# Relay-Board_Rack-PDU_2_0.net
KiCad netlist of a schematic drawn in EAGLE
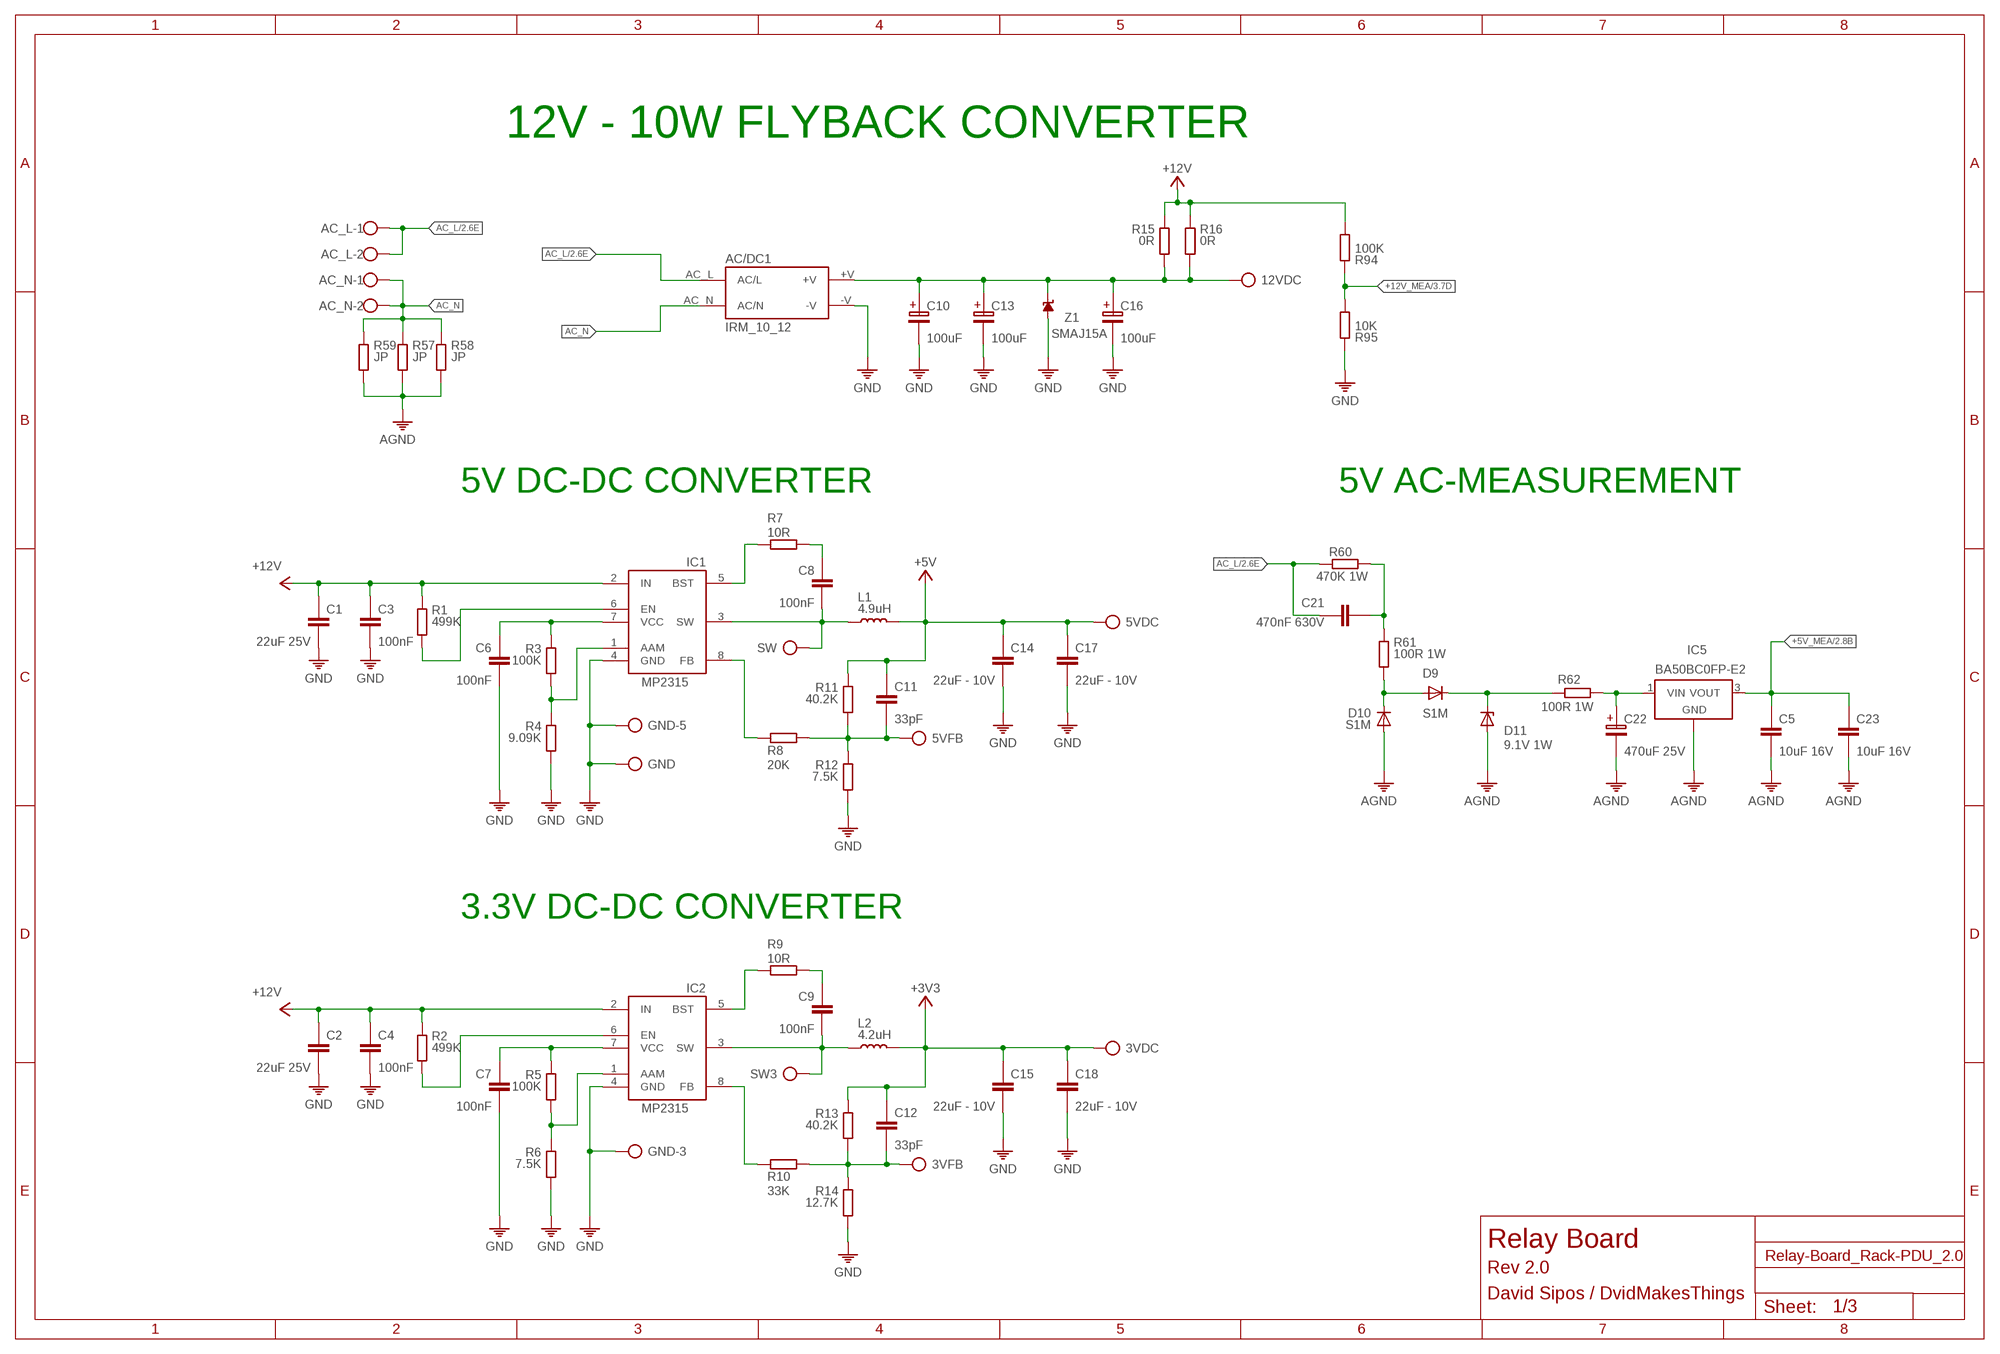
[diagram p0: schematic, sheet 1]
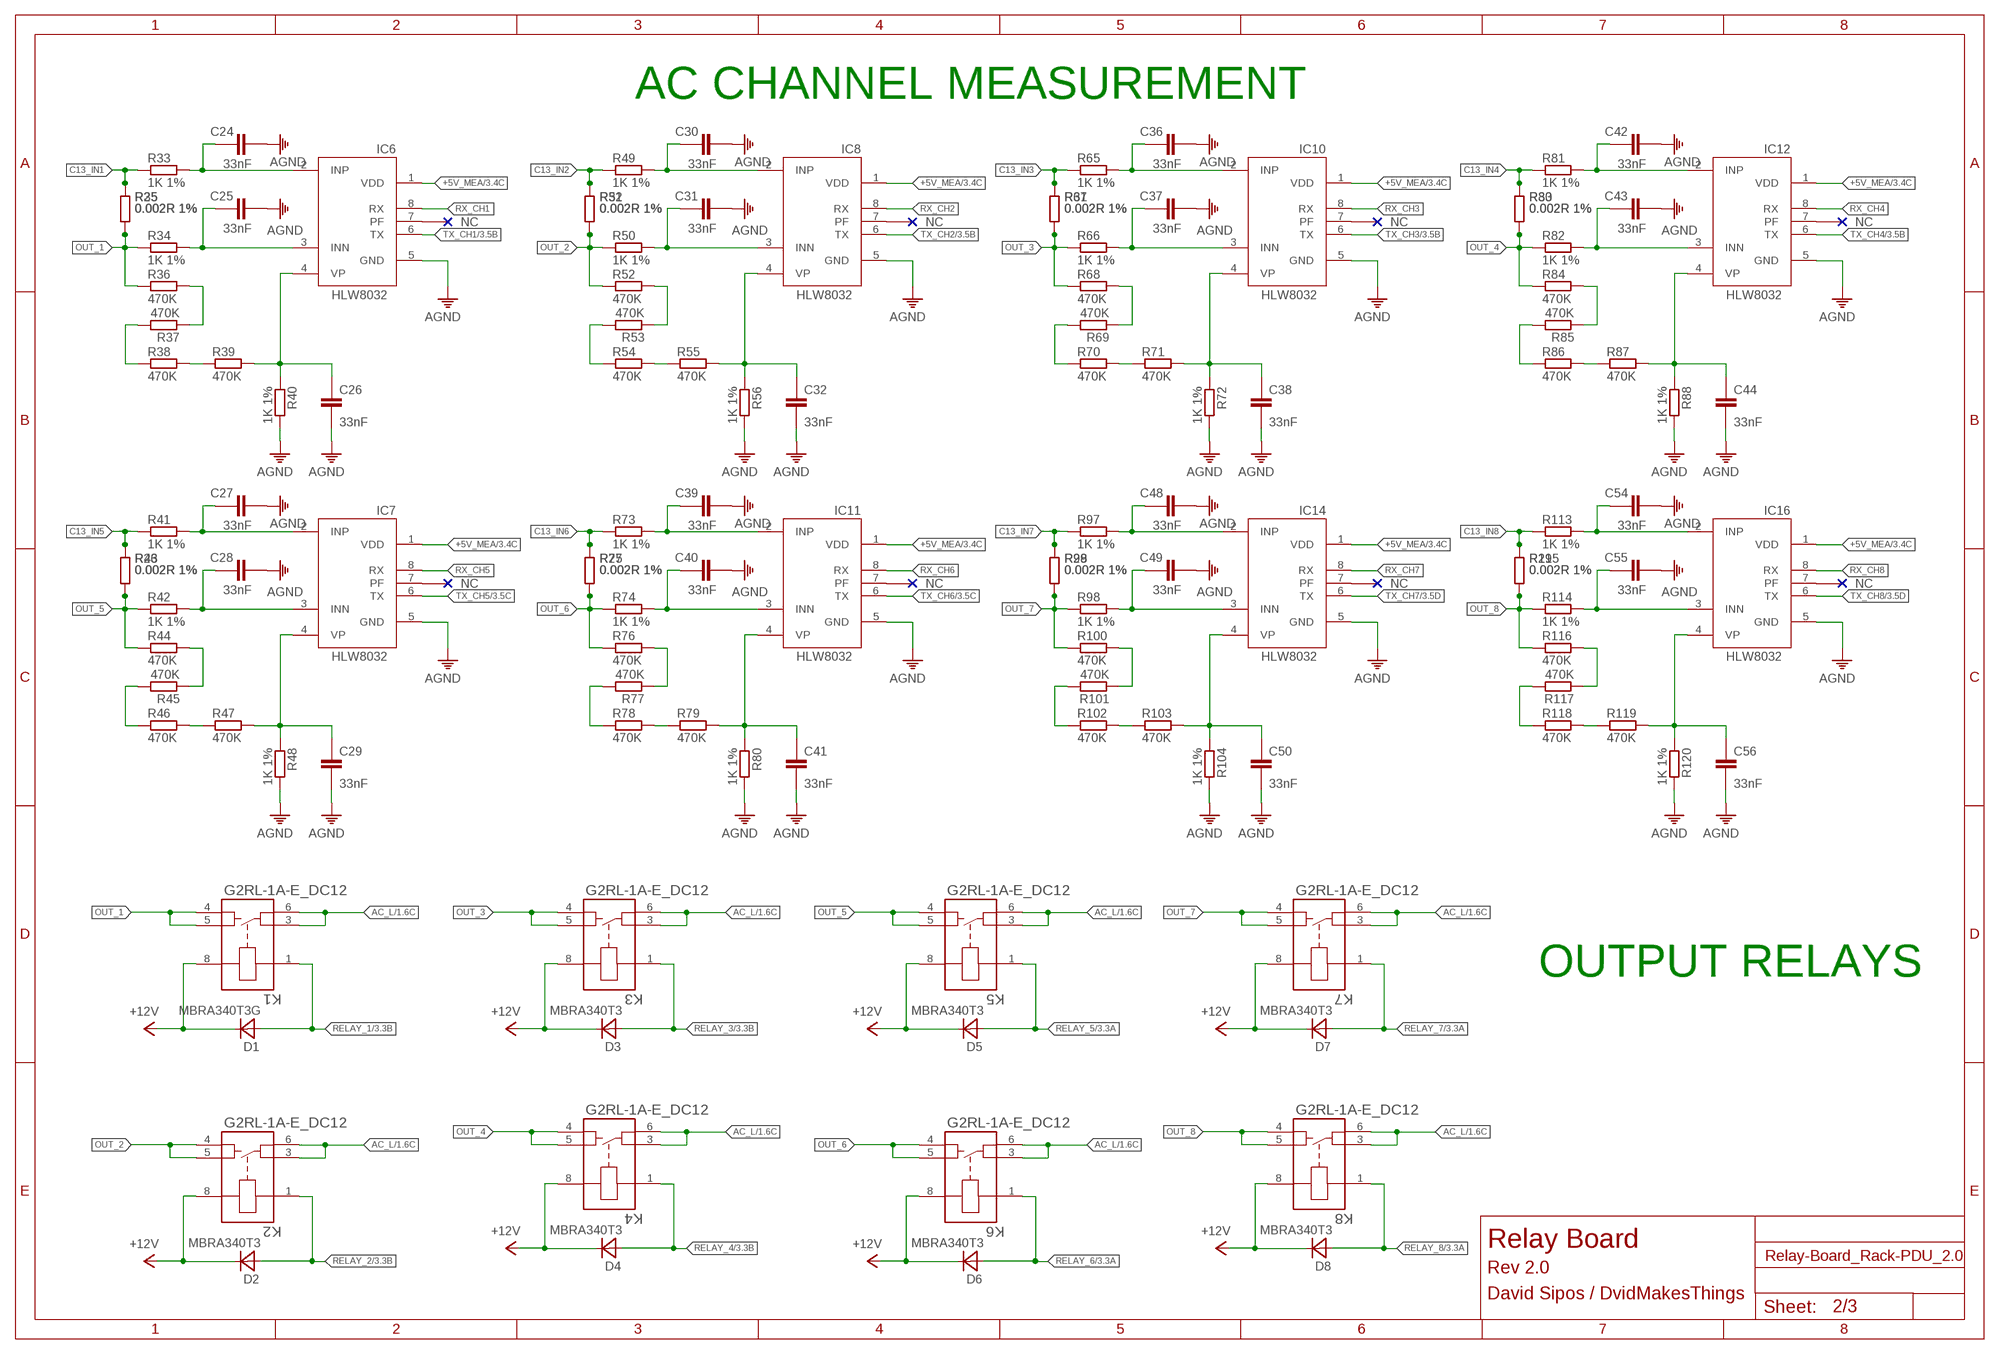
[diagram p1: schematic, sheet 2]
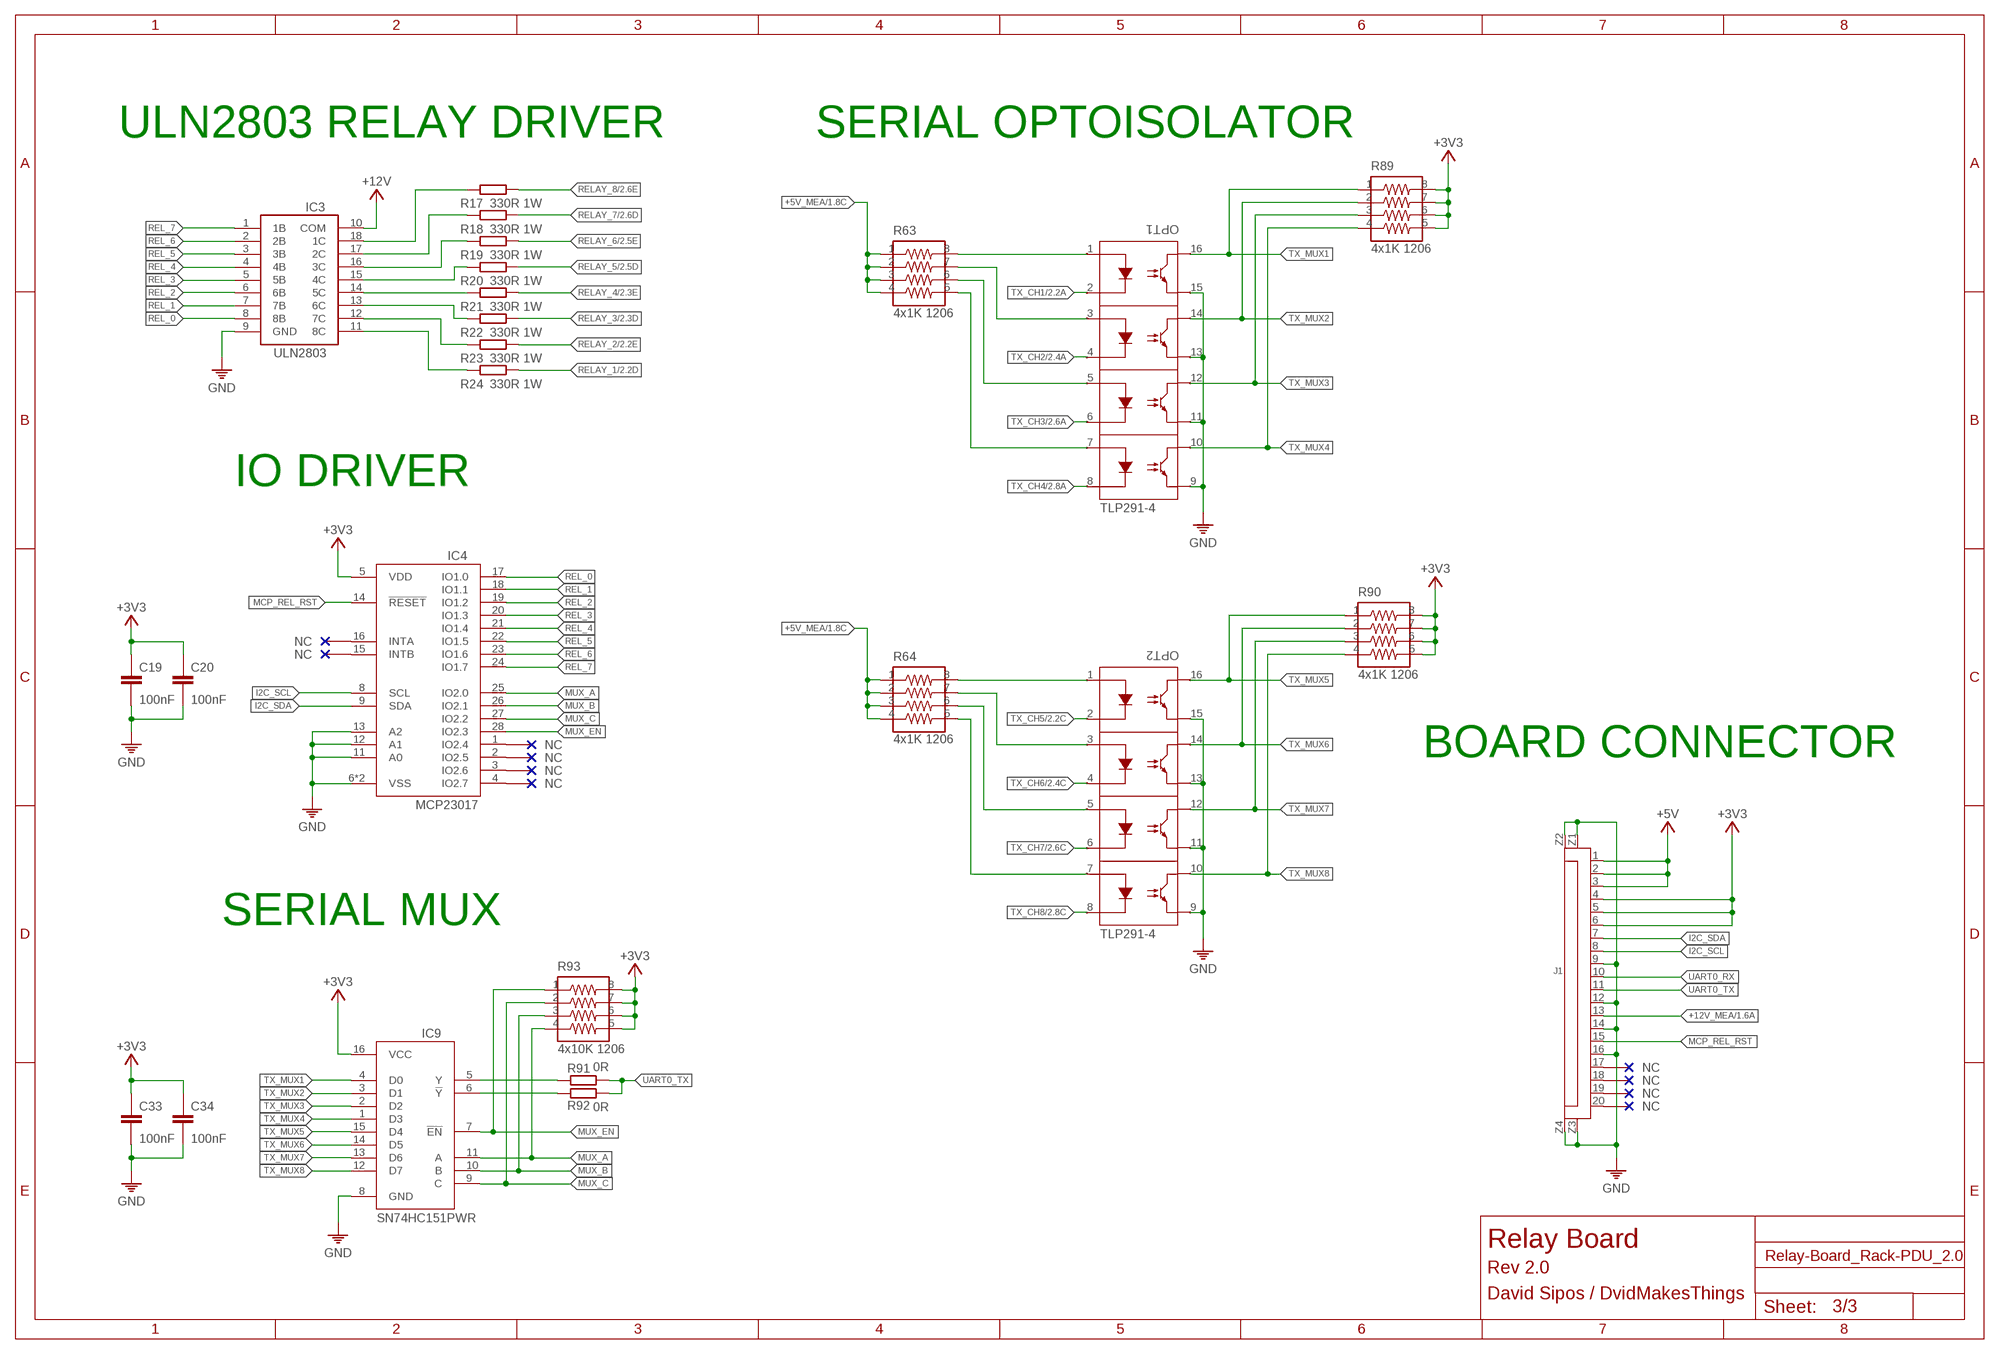
[diagram p2: schematic, sheet 3]

(export (version "E")
  (design (tool "Eeschema 10.0.6"))
  (components
    (comp (ref "C19")
      (value "100nF")
      (footprint "eagle-import:C0402")
      (libsource (lib "eagle-import") (part "C-0402"))
    )
    (comp (ref "C20")
      (value "100nF")
      (footprint "eagle-import:C0402")
      (libsource (lib "eagle-import") (part "C-0402"))
    )
    (comp (ref "C33")
      (value "100nF")
      (footprint "eagle-import:C0402")
      (libsource (lib "eagle-import") (part "C-0402"))
    )
    (comp (ref "C34")
      (value "100nF")
      (footprint "eagle-import:C0402")
      (libsource (lib "eagle-import") (part "C-0402"))
    )
    (comp (ref "IC3")
      (value "ULN2803A")
      (footprint "eagle-import:SO18")
      (libsource (lib "eagle-import") (part "ULN2803"))
    )
    (comp (ref "IC4")
      (value "MCP23017-E/ML")
      (footprint "eagle-import:QFN28[6X6]ML")
      (libsource (lib "eagle-import") (part "MCP23017-E/ML"))
    )
    (comp (ref "IC9")
      (value "SN74HC151PWR")
      (footprint "eagle-import:TSSOP16")
      (libsource (lib "eagle-import") (part "SN74HC151PWR"))
    )
    (comp (ref "J1")
      (value "FPC20-H")
      (footprint "eagle-import:FPC20")
      (libsource (lib "eagle-import") (part "FPC20-H"))
    )
    (comp (ref "OPT1")
      (value "TLP291-4")
      (footprint "eagle-import:SO16")
      (libsource (lib "eagle-import") (part "TLP291-4(GB-TP,E)1"))
    )
    (comp (ref "OPT2")
      (value "TLP291-4")
      (footprint "eagle-import:SO16")
      (libsource (lib "eagle-import") (part "TLP291-4(GB-TP,E)1"))
    )
    (comp (ref "R17")
      (value "330R 1W")
      (footprint "eagle-import:1206")
      (libsource (lib "eagle-import") (part "R1206"))
    )
    (comp (ref "R18")
      (value "330R 1W")
      (footprint "eagle-import:1206")
      (libsource (lib "eagle-import") (part "R1206"))
    )
    (comp (ref "R19")
      (value "330R 1W")
      (footprint "eagle-import:1206")
      (libsource (lib "eagle-import") (part "R1206"))
    )
    (comp (ref "R20")
      (value "330R 1W")
      (footprint "eagle-import:1206")
      (libsource (lib "eagle-import") (part "R1206"))
    )
    (comp (ref "R21")
      (value "330R 1W")
      (footprint "eagle-import:1206")
      (libsource (lib "eagle-import") (part "R1206"))
    )
    (comp (ref "R22")
      (value "330R 1W")
      (footprint "eagle-import:1206")
      (libsource (lib "eagle-import") (part "R1206"))
    )
    (comp (ref "R23")
      (value "330R 1W")
      (footprint "eagle-import:1206")
      (libsource (lib "eagle-import") (part "R1206"))
    )
    (comp (ref "R24")
      (value "330R 1W")
      (footprint "eagle-import:1206")
      (libsource (lib "eagle-import") (part "R1206"))
    )
    (comp (ref "R63")
      (value "4x1K 1206")
      (footprint "eagle-import:742C083103JP")
      (fields
        (field (name "MANUFACTURER") "CTS Resistor Products")
        (field (name "MPN") "742C083103JP")
        (field (name "CREATED_BY") "PCBLayout.com")
      )
      (libsource (lib "eagle-import") (part "742C083103JP"))
    )
    (comp (ref "R64")
      (value "4x1K 1206")
      (footprint "eagle-import:742C083103JP")
      (fields
        (field (name "MANUFACTURER") "CTS Resistor Products")
        (field (name "MPN") "742C083103JP")
        (field (name "CREATED_BY") "PCBLayout.com")
      )
      (libsource (lib "eagle-import") (part "742C083103JP"))
    )
    (comp (ref "R89")
      (value "4x1K 1206")
      (footprint "eagle-import:742C083103JP")
      (fields
        (field (name "MANUFACTURER") "CTS Resistor Products")
        (field (name "MPN") "742C083103JP")
        (field (name "CREATED_BY") "PCBLayout.com")
      )
      (libsource (lib "eagle-import") (part "742C083103JP"))
    )
    (comp (ref "R90")
      (value "4x1K 1206")
      (footprint "eagle-import:742C083103JP")
      (fields
        (field (name "MANUFACTURER") "CTS Resistor Products")
        (field (name "MPN") "742C083103JP")
        (field (name "CREATED_BY") "PCBLayout.com")
      )
      (libsource (lib "eagle-import") (part "742C083103JP"))
    )
    (comp (ref "R91")
      (value "0R")
      (footprint "eagle-import:0402")
      (libsource (lib "eagle-import") (part "R0402"))
    )
    (comp (ref "R92")
      (value "0R")
      (footprint "eagle-import:0402")
      (libsource (lib "eagle-import") (part "R0402"))
    )
    (comp (ref "R93")
      (value "4x10K 1206")
      (footprint "eagle-import:742C083103JP")
      (fields
        (field (name "MANUFACTURER") "CTS Resistor Products")
        (field (name "MPN") "742C083103JP")
        (field (name "CREATED_BY") "PCBLayout.com")
      )
      (libsource (lib "eagle-import") (part "742C083103JP"))
    )
    (comp (ref "C24")
      (value "33nF")
      (footprint "eagle-import:C1206")
      (libsource (lib "eagle-import") (part "C-1206"))
    )
    (comp (ref "C25")
      (value "33nF")
      (footprint "eagle-import:C1206")
      (libsource (lib "eagle-import") (part "C-1206"))
    )
    (comp (ref "C26")
      (value "33nF")
      (footprint "eagle-import:C1206")
      (libsource (lib "eagle-import") (part "C-1206"))
    )
    (comp (ref "C27")
      (value "33nF")
      (footprint "eagle-import:C1206")
      (libsource (lib "eagle-import") (part "C-1206"))
    )
    (comp (ref "C28")
      (value "33nF")
      (footprint "eagle-import:C1206")
      (libsource (lib "eagle-import") (part "C-1206"))
    )
    (comp (ref "C29")
      (value "33nF")
      (footprint "eagle-import:C1206")
      (libsource (lib "eagle-import") (part "C-1206"))
    )
    (comp (ref "C30")
      (value "33nF")
      (footprint "eagle-import:C1206")
      (libsource (lib "eagle-import") (part "C-1206"))
    )
    (comp (ref "C31")
      (value "33nF")
      (footprint "eagle-import:C1206")
      (libsource (lib "eagle-import") (part "C-1206"))
    )
    (comp (ref "C32")
      (value "33nF")
      (footprint "eagle-import:C1206")
      (libsource (lib "eagle-import") (part "C-1206"))
    )
    (comp (ref "C36")
      (value "33nF")
      (footprint "eagle-import:C1206")
      (libsource (lib "eagle-import") (part "C-1206"))
    )
    (comp (ref "C37")
      (value "33nF")
      (footprint "eagle-import:C1206")
      (libsource (lib "eagle-import") (part "C-1206"))
    )
    (comp (ref "C38")
      (value "33nF")
      (footprint "eagle-import:C1206")
      (libsource (lib "eagle-import") (part "C-1206"))
    )
    (comp (ref "C39")
      (value "33nF")
      (footprint "eagle-import:C1206")
      (libsource (lib "eagle-import") (part "C-1206"))
    )
    (comp (ref "C40")
      (value "33nF")
      (footprint "eagle-import:C1206")
      (libsource (lib "eagle-import") (part "C-1206"))
    )
    (comp (ref "C41")
      (value "33nF")
      (footprint "eagle-import:C1206")
      (libsource (lib "eagle-import") (part "C-1206"))
    )
    (comp (ref "C42")
      (value "33nF")
      (footprint "eagle-import:C1206")
      (libsource (lib "eagle-import") (part "C-1206"))
    )
    (comp (ref "C43")
      (value "33nF")
      (footprint "eagle-import:C1206")
      (libsource (lib "eagle-import") (part "C-1206"))
    )
    (comp (ref "C44")
      (value "33nF")
      (footprint "eagle-import:C1206")
      (libsource (lib "eagle-import") (part "C-1206"))
    )
    (comp (ref "C48")
      (value "33nF")
      (footprint "eagle-import:C1206")
      (libsource (lib "eagle-import") (part "C-1206"))
    )
    (comp (ref "C49")
      (value "33nF")
      (footprint "eagle-import:C1206")
      (libsource (lib "eagle-import") (part "C-1206"))
    )
    (comp (ref "C50")
      (value "33nF")
      (footprint "eagle-import:C1206")
      (libsource (lib "eagle-import") (part "C-1206"))
    )
    (comp (ref "C54")
      (value "33nF")
      (footprint "eagle-import:C1206")
      (libsource (lib "eagle-import") (part "C-1206"))
    )
    (comp (ref "C55")
      (value "33nF")
      (footprint "eagle-import:C1206")
      (libsource (lib "eagle-import") (part "C-1206"))
    )
    (comp (ref "C56")
      (value "33nF")
      (footprint "eagle-import:C1206")
      (libsource (lib "eagle-import") (part "C-1206"))
    )
    (comp (ref "D1")
      (value "MBRA340T3G")
      (footprint "eagle-import:SMA")
      (libsource (lib "eagle-import") (part "MBRA340T3"))
    )
    (comp (ref "D2")
      (value "MBRA340T3")
      (footprint "eagle-import:SMA")
      (libsource (lib "eagle-import") (part "MBRA340T3"))
    )
    (comp (ref "D3")
      (value "MBRA340T3")
      (footprint "eagle-import:SMA")
      (libsource (lib "eagle-import") (part "MBRA340T3"))
    )
    (comp (ref "D4")
      (value "MBRA340T3")
      (footprint "eagle-import:SMA")
      (libsource (lib "eagle-import") (part "MBRA340T3"))
    )
    (comp (ref "D5")
      (value "MBRA340T3")
      (footprint "eagle-import:SMA")
      (libsource (lib "eagle-import") (part "MBRA340T3"))
    )
    (comp (ref "D6")
      (value "MBRA340T3")
      (footprint "eagle-import:SMA")
      (libsource (lib "eagle-import") (part "MBRA340T3"))
    )
    (comp (ref "D7")
      (value "MBRA340T3")
      (footprint "eagle-import:SMA")
      (libsource (lib "eagle-import") (part "MBRA340T3"))
    )
    (comp (ref "D8")
      (value "MBRA340T3")
      (footprint "eagle-import:SMA")
      (libsource (lib "eagle-import") (part "MBRA340T3"))
    )
    (comp (ref "IC6")
      (value "HLW8032")
      (footprint "eagle-import:SO8")
      (libsource (lib "eagle-import") (part "HLW8032"))
    )
    (comp (ref "IC7")
      (value "HLW8032")
      (footprint "eagle-import:SO8")
      (libsource (lib "eagle-import") (part "HLW8032"))
    )
    (comp (ref "IC8")
      (value "HLW8032")
      (footprint "eagle-import:SO8")
      (libsource (lib "eagle-import") (part "HLW8032"))
    )
    (comp (ref "IC10")
      (value "HLW8032")
      (footprint "eagle-import:SO8")
      (libsource (lib "eagle-import") (part "HLW8032"))
    )
    (comp (ref "IC11")
      (value "HLW8032")
      (footprint "eagle-import:SO8")
      (libsource (lib "eagle-import") (part "HLW8032"))
    )
    (comp (ref "IC12")
      (value "HLW8032")
      (footprint "eagle-import:SO8")
      (libsource (lib "eagle-import") (part "HLW8032"))
    )
    (comp (ref "IC14")
      (value "HLW8032")
      (footprint "eagle-import:SO8")
      (libsource (lib "eagle-import") (part "HLW8032"))
    )
    (comp (ref "IC16")
      (value "HLW8032")
      (footprint "eagle-import:SO8")
      (libsource (lib "eagle-import") (part "HLW8032"))
    )
    (comp (ref "K1")
      (value "G2RL-1A-E_DC12")
      (footprint "eagle-import:RELAY_G2RL-1A-E_DC5_OMR")
      (fields
        (field (name "MANUFACTURER_PART_NUMBER") "G2RL-1A-E DC12")
        (field (name "COPYRIGHT") "Copyright (C) 2025 Ultra Librarian. All rights reserved.")
      )
      (libsource (lib "eagle-import") (part "G2RL-1A-E_DC12"))
    )
    (comp (ref "K2")
      (value "G2RL-1A-E_DC12")
      (footprint "eagle-import:RELAY_G2RL-1A-E_DC5_OMR")
      (fields
        (field (name "MANUFACTURER_PART_NUMBER") "G2RL-1A-E DC12")
        (field (name "COPYRIGHT") "Copyright (C) 2025 Ultra Librarian. All rights reserved.")
      )
      (libsource (lib "eagle-import") (part "G2RL-1A-E_DC12"))
    )
    (comp (ref "K3")
      (value "G2RL-1A-E_DC12")
      (footprint "eagle-import:RELAY_G2RL-1A-E_DC5_OMR")
      (fields
        (field (name "MANUFACTURER_PART_NUMBER") "G2RL-1A-E DC12")
        (field (name "COPYRIGHT") "Copyright (C) 2025 Ultra Librarian. All rights reserved.")
      )
      (libsource (lib "eagle-import") (part "G2RL-1A-E_DC12"))
    )
    (comp (ref "K4")
      (value "G2RL-1A-E_DC12")
      (footprint "eagle-import:RELAY_G2RL-1A-E_DC5_OMR")
      (fields
        (field (name "MANUFACTURER_PART_NUMBER") "G2RL-1A-E DC12")
        (field (name "COPYRIGHT") "Copyright (C) 2025 Ultra Librarian. All rights reserved.")
      )
      (libsource (lib "eagle-import") (part "G2RL-1A-E_DC12"))
    )
    (comp (ref "K5")
      (value "G2RL-1A-E_DC12")
      (footprint "eagle-import:RELAY_G2RL-1A-E_DC5_OMR")
      (fields
        (field (name "MANUFACTURER_PART_NUMBER") "G2RL-1A-E DC12")
        (field (name "COPYRIGHT") "Copyright (C) 2025 Ultra Librarian. All rights reserved.")
      )
      (libsource (lib "eagle-import") (part "G2RL-1A-E_DC12"))
    )
    (comp (ref "K6")
      (value "G2RL-1A-E_DC12")
      (footprint "eagle-import:RELAY_G2RL-1A-E_DC5_OMR")
      (fields
        (field (name "MANUFACTURER_PART_NUMBER") "G2RL-1A-E DC12")
        (field (name "COPYRIGHT") "Copyright (C) 2025 Ultra Librarian. All rights reserved.")
      )
      (libsource (lib "eagle-import") (part "G2RL-1A-E_DC12"))
    )
    (comp (ref "K7")
      (value "G2RL-1A-E_DC12")
      (footprint "eagle-import:RELAY_G2RL-1A-E_DC5_OMR")
      (fields
        (field (name "MANUFACTURER_PART_NUMBER") "G2RL-1A-E DC12")
        (field (name "COPYRIGHT") "Copyright (C) 2025 Ultra Librarian. All rights reserved.")
      )
      (libsource (lib "eagle-import") (part "G2RL-1A-E_DC12"))
    )
    (comp (ref "K8")
      (value "G2RL-1A-E_DC12")
      (footprint "eagle-import:RELAY_G2RL-1A-E_DC5_OMR")
      (fields
        (field (name "MANUFACTURER_PART_NUMBER") "G2RL-1A-E DC12")
        (field (name "COPYRIGHT") "Copyright (C) 2025 Ultra Librarian. All rights reserved.")
      )
      (libsource (lib "eagle-import") (part "G2RL-1A-E_DC12"))
    )
    (comp (ref "R25")
      (value "0.002R 1%")
      (footprint "eagle-import:2512")
      (libsource (lib "eagle-import") (part "R2512"))
    )
    (comp (ref "R26")
      (value "0.002R 1%")
      (footprint "eagle-import:2512")
      (libsource (lib "eagle-import") (part "R2512"))
    )
    (comp (ref "R27")
      (value "0.002R 1%")
      (footprint "eagle-import:2512")
      (libsource (lib "eagle-import") (part "R2512"))
    )
    (comp (ref "R28")
      (value "0.002R 1%")
      (footprint "eagle-import:2512")
      (libsource (lib "eagle-import") (part "R2512"))
    )
    (comp (ref "R29")
      (value "0.002R 1%")
      (footprint "eagle-import:2512")
      (libsource (lib "eagle-import") (part "R2512"))
    )
    (comp (ref "R30")
      (value "0.002R 1%")
      (footprint "eagle-import:2512")
      (libsource (lib "eagle-import") (part "R2512"))
    )
    (comp (ref "R31")
      (value "0.002R 1%")
      (footprint "eagle-import:2512")
      (libsource (lib "eagle-import") (part "R2512"))
    )
    (comp (ref "R32")
      (value "0.002R 1%")
      (footprint "eagle-import:2512")
      (libsource (lib "eagle-import") (part "R2512"))
    )
    (comp (ref "R33")
      (value "1K 1%")
      (footprint "eagle-import:1206")
      (libsource (lib "eagle-import") (part "R1206"))
    )
    (comp (ref "R34")
      (value "1K 1%")
      (footprint "eagle-import:1206")
      (libsource (lib "eagle-import") (part "R1206"))
    )
    (comp (ref "R35")
      (value "0.002R 1%")
      (footprint "eagle-import:2512")
      (libsource (lib "eagle-import") (part "R2512"))
    )
    (comp (ref "R36")
      (value "470K")
      (footprint "eagle-import:1206")
      (libsource (lib "eagle-import") (part "R1206"))
    )
    (comp (ref "R37")
      (value "470K")
      (footprint "eagle-import:1206")
      (libsource (lib "eagle-import") (part "R1206"))
    )
    (comp (ref "R38")
      (value "470K")
      (footprint "eagle-import:1206")
      (libsource (lib "eagle-import") (part "R1206"))
    )
    (comp (ref "R39")
      (value "470K")
      (footprint "eagle-import:1206")
      (libsource (lib "eagle-import") (part "R1206"))
    )
    (comp (ref "R40")
      (value "1K 1%")
      (footprint "eagle-import:1206")
      (libsource (lib "eagle-import") (part "R1206"))
    )
    (comp (ref "R41")
      (value "1K 1%")
      (footprint "eagle-import:1206")
      (libsource (lib "eagle-import") (part "R1206"))
    )
    (comp (ref "R42")
      (value "1K 1%")
      (footprint "eagle-import:1206")
      (libsource (lib "eagle-import") (part "R1206"))
    )
    (comp (ref "R43")
      (value "0.002R 1%")
      (footprint "eagle-import:2512")
      (libsource (lib "eagle-import") (part "R2512"))
    )
    (comp (ref "R44")
      (value "470K")
      (footprint "eagle-import:1206")
      (libsource (lib "eagle-import") (part "R1206"))
    )
    (comp (ref "R45")
      (value "470K")
      (footprint "eagle-import:1206")
      (libsource (lib "eagle-import") (part "R1206"))
    )
    (comp (ref "R46")
      (value "470K")
      (footprint "eagle-import:1206")
      (libsource (lib "eagle-import") (part "R1206"))
    )
    (comp (ref "R47")
      (value "470K")
      (footprint "eagle-import:1206")
      (libsource (lib "eagle-import") (part "R1206"))
    )
    (comp (ref "R48")
      (value "1K 1%")
      (footprint "eagle-import:1206")
      (libsource (lib "eagle-import") (part "R1206"))
    )
    (comp (ref "R49")
      (value "1K 1%")
      (footprint "eagle-import:1206")
      (libsource (lib "eagle-import") (part "R1206"))
    )
    (comp (ref "R50")
      (value "1K 1%")
      (footprint "eagle-import:1206")
      (libsource (lib "eagle-import") (part "R1206"))
    )
    (comp (ref "R51")
      (value "0.002R 1%")
      (footprint "eagle-import:2512")
      (libsource (lib "eagle-import") (part "R2512"))
    )
    (comp (ref "R52")
      (value "470K")
      (footprint "eagle-import:1206")
      (libsource (lib "eagle-import") (part "R1206"))
    )
    (comp (ref "R53")
      (value "470K")
      (footprint "eagle-import:1206")
      (libsource (lib "eagle-import") (part "R1206"))
    )
    (comp (ref "R54")
      (value "470K")
      (footprint "eagle-import:1206")
      (libsource (lib "eagle-import") (part "R1206"))
    )
    (comp (ref "R55")
      (value "470K")
      (footprint "eagle-import:1206")
      (libsource (lib "eagle-import") (part "R1206"))
    )
    (comp (ref "R56")
      (value "1K 1%")
      (footprint "eagle-import:1206")
      (libsource (lib "eagle-import") (part "R1206"))
    )
    (comp (ref "R65")
      (value "1K 1%")
      (footprint "eagle-import:1206")
      (libsource (lib "eagle-import") (part "R1206"))
    )
    (comp (ref "R66")
      (value "1K 1%")
      (footprint "eagle-import:1206")
      (libsource (lib "eagle-import") (part "R1206"))
    )
    (comp (ref "R67")
      (value "0.002R 1%")
      (footprint "eagle-import:2512")
      (libsource (lib "eagle-import") (part "R2512"))
    )
    (comp (ref "R68")
      (value "470K")
      (footprint "eagle-import:1206")
      (libsource (lib "eagle-import") (part "R1206"))
    )
    (comp (ref "R69")
      (value "470K")
      (footprint "eagle-import:1206")
      (libsource (lib "eagle-import") (part "R1206"))
    )
    (comp (ref "R70")
      (value "470K")
      (footprint "eagle-import:1206")
      (libsource (lib "eagle-import") (part "R1206"))
    )
    (comp (ref "R71")
      (value "470K")
      (footprint "eagle-import:1206")
      (libsource (lib "eagle-import") (part "R1206"))
    )
    (comp (ref "R72")
      (value "1K 1%")
      (footprint "eagle-import:1206")
      (libsource (lib "eagle-import") (part "R1206"))
    )
    (comp (ref "R73")
      (value "1K 1%")
      (footprint "eagle-import:1206")
      (libsource (lib "eagle-import") (part "R1206"))
    )
    (comp (ref "R74")
      (value "1K 1%")
      (footprint "eagle-import:1206")
      (libsource (lib "eagle-import") (part "R1206"))
    )
    (comp (ref "R75")
      (value "0.002R 1%")
      (footprint "eagle-import:2512")
      (libsource (lib "eagle-import") (part "R2512"))
    )
    (comp (ref "R76")
      (value "470K")
      (footprint "eagle-import:1206")
      (libsource (lib "eagle-import") (part "R1206"))
    )
    (comp (ref "R77")
      (value "470K")
      (footprint "eagle-import:1206")
      (libsource (lib "eagle-import") (part "R1206"))
    )
    (comp (ref "R78")
      (value "470K")
      (footprint "eagle-import:1206")
      (libsource (lib "eagle-import") (part "R1206"))
    )
    (comp (ref "R79")
      (value "470K")
      (footprint "eagle-import:1206")
      (libsource (lib "eagle-import") (part "R1206"))
    )
    (comp (ref "R80")
      (value "1K 1%")
      (footprint "eagle-import:1206")
      (libsource (lib "eagle-import") (part "R1206"))
    )
    (comp (ref "R81")
      (value "1K 1%")
      (footprint "eagle-import:1206")
      (libsource (lib "eagle-import") (part "R1206"))
    )
    (comp (ref "R82")
      (value "1K 1%")
      (footprint "eagle-import:1206")
      (libsource (lib "eagle-import") (part "R1206"))
    )
    (comp (ref "R83")
      (value "0.002R 1%")
      (footprint "eagle-import:2512")
      (libsource (lib "eagle-import") (part "R2512"))
    )
    (comp (ref "R84")
      (value "470K")
      (footprint "eagle-import:1206")
      (libsource (lib "eagle-import") (part "R1206"))
    )
    (comp (ref "R85")
      (value "470K")
      (footprint "eagle-import:1206")
      (libsource (lib "eagle-import") (part "R1206"))
    )
    (comp (ref "R86")
      (value "470K")
      (footprint "eagle-import:1206")
      (libsource (lib "eagle-import") (part "R1206"))
    )
    (comp (ref "R87")
      (value "470K")
      (footprint "eagle-import:1206")
      (libsource (lib "eagle-import") (part "R1206"))
    )
    (comp (ref "R88")
      (value "1K 1%")
      (footprint "eagle-import:1206")
      (libsource (lib "eagle-import") (part "R1206"))
    )
    (comp (ref "R97")
      (value "1K 1%")
      (footprint "eagle-import:1206")
      (libsource (lib "eagle-import") (part "R1206"))
    )
    (comp (ref "R98")
      (value "1K 1%")
      (footprint "eagle-import:1206")
      (libsource (lib "eagle-import") (part "R1206"))
    )
    (comp (ref "R99")
      (value "0.002R 1%")
      (footprint "eagle-import:2512")
      (libsource (lib "eagle-import") (part "R2512"))
    )
    (comp (ref "R100")
      (value "470K")
      (footprint "eagle-import:1206")
      (libsource (lib "eagle-import") (part "R1206"))
    )
    (comp (ref "R101")
      (value "470K")
      (footprint "eagle-import:1206")
      (libsource (lib "eagle-import") (part "R1206"))
    )
    (comp (ref "R102")
      (value "470K")
      (footprint "eagle-import:1206")
      (libsource (lib "eagle-import") (part "R1206"))
    )
    (comp (ref "R103")
      (value "470K")
      (footprint "eagle-import:1206")
      (libsource (lib "eagle-import") (part "R1206"))
    )
    (comp (ref "R104")
      (value "1K 1%")
      (footprint "eagle-import:1206")
      (libsource (lib "eagle-import") (part "R1206"))
    )
    (comp (ref "R113")
      (value "1K 1%")
      (footprint "eagle-import:1206")
      (libsource (lib "eagle-import") (part "R1206"))
    )
    (comp (ref "R114")
      (value "1K 1%")
      (footprint "eagle-import:1206")
      (libsource (lib "eagle-import") (part "R1206"))
    )
    (comp (ref "R115")
      (value "0.002R 1%")
      (footprint "eagle-import:2512")
      (libsource (lib "eagle-import") (part "R2512"))
    )
    (comp (ref "R116")
      (value "470K")
      (footprint "eagle-import:1206")
      (libsource (lib "eagle-import") (part "R1206"))
    )
    (comp (ref "R117")
      (value "470K")
      (footprint "eagle-import:1206")
      (libsource (lib "eagle-import") (part "R1206"))
    )
    (comp (ref "R118")
      (value "470K")
      (footprint "eagle-import:1206")
      (libsource (lib "eagle-import") (part "R1206"))
    )
    (comp (ref "R119")
      (value "470K")
      (footprint "eagle-import:1206")
      (libsource (lib "eagle-import") (part "R1206"))
    )
    (comp (ref "R120")
      (value "1K 1%")
      (footprint "eagle-import:1206")
      (libsource (lib "eagle-import") (part "R1206"))
    )
    (comp (ref "3VDC")
      (value "TP")
      (footprint "eagle-import:TP")
      (libsource (lib "eagle-import") (part "TP"))
    )
    (comp (ref "3VFB")
      (value "TP")
      (footprint "eagle-import:TP")
      (libsource (lib "eagle-import") (part "TP"))
    )
    (comp (ref "5VDC")
      (value "TP")
      (footprint "eagle-import:TP")
      (libsource (lib "eagle-import") (part "TP"))
    )
    (comp (ref "5VFB")
      (value "TP")
      (footprint "eagle-import:TP")
      (libsource (lib "eagle-import") (part "TP"))
    )
    (comp (ref "12VDC")
      (value "TP")
      (footprint "eagle-import:TP")
      (libsource (lib "eagle-import") (part "TP"))
    )
    (comp (ref "AC/DC1")
      (value "IRM_10_12")
      (footprint "eagle-import:IRM_10_12")
      (libsource (lib "eagle-import") (part "IRM_10_12"))
    )
    (comp (ref "AC_L")
      (value "W237-102")
      (footprint "eagle-import:W237-102")
      (fields (field (name "MPN") "237-102"))
      (libsource (lib "eagle-import") (part "W237-102"))
    )
    (comp (ref "AC_N")
      (value "W237-102")
      (footprint "eagle-import:W237-102")
      (fields (field (name "MPN") "237-102"))
      (libsource (lib "eagle-import") (part "W237-102"))
    )
    (comp (ref "C1")
      (value "22uF 25V")
      (footprint "eagle-import:C1206")
      (libsource (lib "eagle-import") (part "C-1206"))
    )
    (comp (ref "C2")
      (value "22uF 25V")
      (footprint "eagle-import:C1206")
      (libsource (lib "eagle-import") (part "C-1206"))
    )
    (comp (ref "C3")
      (value "100nF")
      (footprint "eagle-import:0402")
      (libsource (lib "eagle-import") (part "C0402"))
    )
    (comp (ref "C4")
      (value "100nF")
      (footprint "eagle-import:0402")
      (libsource (lib "eagle-import") (part "C0402"))
    )
    (comp (ref "C5")
      (value "10uF 16V")
      (footprint "eagle-import:C1206")
      (libsource (lib "eagle-import") (part "C-1206"))
    )
    (comp (ref "C6")
      (value "100nF")
      (footprint "eagle-import:0402")
      (libsource (lib "eagle-import") (part "C0402"))
    )
    (comp (ref "C7")
      (value "100nF")
      (footprint "eagle-import:0402")
      (libsource (lib "eagle-import") (part "C0402"))
    )
    (comp (ref "C8")
      (value "100nF")
      (footprint "eagle-import:0402")
      (libsource (lib "eagle-import") (part "C0402"))
    )
    (comp (ref "C9")
      (value "100nF")
      (footprint "eagle-import:0402")
      (libsource (lib "eagle-import") (part "C0402"))
    )
    (comp (ref "C10")
      (value "100uF")
      (footprint "eagle-import:100UF-16V")
      (libsource (lib "eagle-import") (part "CPOL"))
    )
    (comp (ref "C11")
      (value "33pF")
      (footprint "eagle-import:0402")
      (libsource (lib "eagle-import") (part "C0402"))
    )
    (comp (ref "C12")
      (value "33pF")
      (footprint "eagle-import:0402")
      (libsource (lib "eagle-import") (part "C0402"))
    )
    (comp (ref "C13")
      (value "100uF")
      (footprint "eagle-import:100UF-16V")
      (libsource (lib "eagle-import") (part "CPOL"))
    )
    (comp (ref "C14")
      (value "22uF - 10V")
      (footprint "eagle-import:C1206")
      (libsource (lib "eagle-import") (part "C-1206"))
    )
    (comp (ref "C15")
      (value "22uF - 10V")
      (footprint "eagle-import:C1206")
      (libsource (lib "eagle-import") (part "C-1206"))
    )
    (comp (ref "C16")
      (value "100uF")
      (footprint "eagle-import:100UF-16V")
      (libsource (lib "eagle-import") (part "CPOL"))
    )
    (comp (ref "C17")
      (value "22uF - 10V")
      (footprint "eagle-import:C1206")
      (libsource (lib "eagle-import") (part "C-1206"))
    )
    (comp (ref "C18")
      (value "22uF - 10V")
      (footprint "eagle-import:C1206")
      (libsource (lib "eagle-import") (part "C-1206"))
    )
    (comp (ref "C21")
      (value "470nF 630V")
      (footprint "eagle-import:2225")
      (libsource (lib "eagle-import") (part "C-2225"))
    )
    (comp (ref "C22")
      (value "470uF 25V")
      (footprint "eagle-import:100UF-16V")
      (libsource (lib "eagle-import") (part "CPOL"))
    )
    (comp (ref "C23")
      (value "10uF 16V")
      (footprint "eagle-import:C1206")
      (libsource (lib "eagle-import") (part "C-1206"))
    )
    (comp (ref "D9")
      (value "S1M")
      (footprint "eagle-import:SMA")
      (libsource (lib "eagle-import") (part "S1M"))
    )
    (comp (ref "D10")
      (value "S1M")
      (footprint "eagle-import:SMA")
      (libsource (lib "eagle-import") (part "S1M"))
    )
    (comp (ref "D11")
      (value "9.1V 1W")
      (footprint "eagle-import:SMB")
      (libsource (lib "eagle-import") (part "ZENER-DIODESMB"))
    )
    (comp (ref "GND") (value "TP") (footprint "eagle-import:TP") (libsource (lib "eagle-import") (part "TP")))
    (comp (ref "GND-3")
      (value "TP")
      (footprint "eagle-import:TP")
      (libsource (lib "eagle-import") (part "TP"))
    )
    (comp (ref "GND-5")
      (value "TP")
      (footprint "eagle-import:TP")
      (libsource (lib "eagle-import") (part "TP"))
    )
    (comp (ref "IC1")
      (value "MP2315GJ-Z")
      (footprint "eagle-import:SOT65P280X110-8N")
      (libsource (lib "eagle-import") (part "MP2315TSOT23-8"))
    )
    (comp (ref "IC2")
      (value "MP2315S")
      (footprint "eagle-import:SOT65P280X110-8N")
      (libsource (lib "eagle-import") (part "MP2315TSOT23-8"))
    )
    (comp (ref "IC5")
      (value "BA50BC0FP-E2")
      (footprint "eagle-import:DPAK")
      (libsource (lib "eagle-import") (part "L4941BDT"))
    )
    (comp (ref "L1")
      (value "4.9uH")
      (footprint "eagle-import:SRR5228A")
      (libsource (lib "eagle-import") (part "L"))
    )
    (comp (ref "L2")
      (value "4.2uH")
      (footprint "eagle-import:SRR5228A")
      (libsource (lib "eagle-import") (part "L"))
    )
    (comp (ref "R1")
      (value "499K")
      (footprint "eagle-import:0402")
      (libsource (lib "eagle-import") (part "R0402"))
    )
    (comp (ref "R2")
      (value "499K")
      (footprint "eagle-import:0402")
      (libsource (lib "eagle-import") (part "R0402"))
    )
    (comp (ref "R3")
      (value "100K")
      (footprint "eagle-import:0402")
      (libsource (lib "eagle-import") (part "R0402"))
    )
    (comp (ref "R4")
      (value "9.09K")
      (footprint "eagle-import:0402")
      (libsource (lib "eagle-import") (part "R0402"))
    )
    (comp (ref "R5")
      (value "100K")
      (footprint "eagle-import:0402")
      (libsource (lib "eagle-import") (part "R0402"))
    )
    (comp (ref "R6")
      (value "7.5K")
      (footprint "eagle-import:0402")
      (libsource (lib "eagle-import") (part "R0402"))
    )
    (comp (ref "R7")
      (value "10R")
      (footprint "eagle-import:0402")
      (libsource (lib "eagle-import") (part "R0402"))
    )
    (comp (ref "R8")
      (value "20K")
      (footprint "eagle-import:0402")
      (libsource (lib "eagle-import") (part "R0402"))
    )
    (comp (ref "R9")
      (value "10R")
      (footprint "eagle-import:0402")
      (libsource (lib "eagle-import") (part "R0402"))
    )
    (comp (ref "R10")
      (value "33K")
      (footprint "eagle-import:0402")
      (libsource (lib "eagle-import") (part "R0402"))
    )
    (comp (ref "R11")
      (value "40.2K")
      (footprint "eagle-import:0402")
      (libsource (lib "eagle-import") (part "R0402"))
    )
    (comp (ref "R12")
      (value "7.5K")
      (footprint "eagle-import:0402")
      (libsource (lib "eagle-import") (part "R0402"))
    )
    (comp (ref "R13")
      (value "40.2K")
      (footprint "eagle-import:0402")
      (libsource (lib "eagle-import") (part "R0402"))
    )
    (comp (ref "R14")
      (value "12.7K")
      (footprint "eagle-import:0402")
      (libsource (lib "eagle-import") (part "R0402"))
    )
    (comp (ref "R15")
      (value "0R")
      (footprint "eagle-import:0805")
      (libsource (lib "eagle-import") (part "R0805"))
    )
    (comp (ref "R16")
      (value "0R")
      (footprint "eagle-import:0805")
      (libsource (lib "eagle-import") (part "R0805"))
    )
    (comp (ref "R57")
      (value "JP")
      (footprint "eagle-import:0402")
      (libsource (lib "eagle-import") (part "R0402"))
    )
    (comp (ref "R58")
      (value "JP")
      (footprint "eagle-import:0402")
      (libsource (lib "eagle-import") (part "R0402"))
    )
    (comp (ref "R59")
      (value "JP")
      (footprint "eagle-import:0402")
      (libsource (lib "eagle-import") (part "R0402"))
    )
    (comp (ref "R60")
      (value "470K 1W")
      (footprint "eagle-import:2512")
      (libsource (lib "eagle-import") (part "R2512"))
    )
    (comp (ref "R61")
      (value "100R 1W")
      (footprint "eagle-import:2512")
      (libsource (lib "eagle-import") (part "R2512"))
    )
    (comp (ref "R62")
      (value "100R 1W")
      (footprint "eagle-import:2512")
      (libsource (lib "eagle-import") (part "R2512"))
    )
    (comp (ref "R94")
      (value "100K")
      (footprint "eagle-import:0402")
      (libsource (lib "eagle-import") (part "R0402"))
    )
    (comp (ref "R95")
      (value "10K")
      (footprint "eagle-import:0402")
      (libsource (lib "eagle-import") (part "R0402"))
    )
    (comp (ref "SW") (value "TP") (footprint "eagle-import:TP") (libsource (lib "eagle-import") (part "TP")))
    (comp (ref "SW3") (value "TP") (footprint "eagle-import:TP") (libsource (lib "eagle-import") (part "TP")))
    (comp (ref "Z1")
      (value "SMAJ15A")
      (footprint "eagle-import:SUPRESSOR_SMAJ")
      (libsource (lib "eagle-import") (part "SUPRESSOR_TVS-UD-SMAJ"))
    )
  )
  (nets
    (net (code "1") (name "+3V3") (class "Default")
      (node (ref "3VDC") (pin "TP") (pinfunction "P$1_TP") (pintype "bidirectional"))
      (node (ref "C12") (pin "1") (pinfunction "1_1") (pintype "passive"))
      (node (ref "C15") (pin "1") (pinfunction "1_1") (pintype "passive"))
      (node (ref "C18") (pin "1") (pinfunction "1_1") (pintype "passive"))
      (node (ref "C19") (pin "1") (pinfunction "1_1") (pintype "passive"))
      (node (ref "C20") (pin "1") (pinfunction "1_1") (pintype "passive"))
      (node (ref "C33") (pin "1") (pinfunction "1_1") (pintype "passive"))
      (node (ref "C34") (pin "1") (pinfunction "1_1") (pintype "passive"))
      (node (ref "IC4") (pin "5") (pinfunction "VDD_5") (pintype "bidirectional"))
      (node (ref "IC9") (pin "16") (pinfunction "VCC_16") (pintype "power_in"))
      (node (ref "J1") (pin "4") (pinfunction "4_4") (pintype "bidirectional"))
      (node (ref "J1") (pin "5") (pinfunction "5_5") (pintype "bidirectional"))
      (node (ref "J1") (pin "6") (pinfunction "6_6") (pintype "bidirectional"))
      (node (ref "L2") (pin "2") (pinfunction "2_2") (pintype "passive"))
      (node (ref "R13") (pin "1") (pinfunction "1_1") (pintype "passive"))
      (node (ref "R89") (pin "5") (pinfunction "5_5") (pintype "passive"))
      (node (ref "R89") (pin "6") (pinfunction "6_6") (pintype "passive"))
      (node (ref "R89") (pin "7") (pinfunction "7_7") (pintype "passive"))
      (node (ref "R89") (pin "8") (pinfunction "8_8") (pintype "passive"))
      (node (ref "R90") (pin "5") (pinfunction "5_5") (pintype "passive"))
      (node (ref "R90") (pin "6") (pinfunction "6_6") (pintype "passive"))
      (node (ref "R90") (pin "7") (pinfunction "7_7") (pintype "passive"))
      (node (ref "R90") (pin "8") (pinfunction "8_8") (pintype "passive"))
      (node (ref "R93") (pin "5") (pinfunction "5_5") (pintype "passive"))
      (node (ref "R93") (pin "6") (pinfunction "6_6") (pintype "passive"))
      (node (ref "R93") (pin "7") (pinfunction "7_7") (pintype "passive"))
      (node (ref "R93") (pin "8") (pinfunction "8_8") (pintype "passive"))
    )
    (net (code "2") (name "+5V") (class "Default")
      (node (ref "5VDC") (pin "TP") (pinfunction "P$1_TP") (pintype "bidirectional"))
      (node (ref "C11") (pin "1") (pinfunction "1_1") (pintype "passive"))
      (node (ref "C14") (pin "1") (pinfunction "1_1") (pintype "passive"))
      (node (ref "C17") (pin "1") (pinfunction "1_1") (pintype "passive"))
      (node (ref "J1") (pin "1") (pinfunction "1_1") (pintype "bidirectional"))
      (node (ref "J1") (pin "2") (pinfunction "2_2") (pintype "bidirectional"))
      (node (ref "J1") (pin "3") (pinfunction "3_3") (pintype "bidirectional"))
      (node (ref "L1") (pin "2") (pinfunction "2_2") (pintype "passive"))
      (node (ref "R11") (pin "1") (pinfunction "1_1") (pintype "passive"))
    )
    (net (code "3") (name "+5V_MEA") (class "Default")
      (node (ref "C23") (pin "1") (pinfunction "1_1") (pintype "passive"))
      (node (ref "C5") (pin "1") (pinfunction "1_1") (pintype "passive"))
      (node (ref "IC10") (pin "1") (pinfunction "VDD_1") (pintype "power_in"))
      (node (ref "IC11") (pin "1") (pinfunction "VDD_1") (pintype "power_in"))
      (node (ref "IC12") (pin "1") (pinfunction "VDD_1") (pintype "power_in"))
      (node (ref "IC14") (pin "1") (pinfunction "VDD_1") (pintype "power_in"))
      (node (ref "IC16") (pin "1") (pinfunction "VDD_1") (pintype "power_in"))
      (node (ref "IC5") (pin "3") (pinfunction "VOUT_3") (pintype "power_in"))
      (node (ref "IC6") (pin "1") (pinfunction "VDD_1") (pintype "power_in"))
      (node (ref "IC7") (pin "1") (pinfunction "VDD_1") (pintype "power_in"))
      (node (ref "IC8") (pin "1") (pinfunction "VDD_1") (pintype "power_in"))
      (node (ref "R63") (pin "1") (pinfunction "1_1") (pintype "passive"))
      (node (ref "R63") (pin "2") (pinfunction "2_2") (pintype "passive"))
      (node (ref "R63") (pin "3") (pinfunction "3_3") (pintype "passive"))
      (node (ref "R63") (pin "4") (pinfunction "4_4") (pintype "passive"))
      (node (ref "R64") (pin "1") (pinfunction "1_1") (pintype "passive"))
      (node (ref "R64") (pin "2") (pinfunction "2_2") (pintype "passive"))
      (node (ref "R64") (pin "3") (pinfunction "3_3") (pintype "passive"))
      (node (ref "R64") (pin "4") (pinfunction "4_4") (pintype "passive"))
    )
    (net (code "4") (name "+12V") (class "Default")
      (node (ref "C1") (pin "1") (pinfunction "1_1") (pintype "passive"))
      (node (ref "C2") (pin "1") (pinfunction "1_1") (pintype "passive"))
      (node (ref "C3") (pin "1") (pinfunction "1_1") (pintype "passive"))
      (node (ref "C4") (pin "1") (pinfunction "1_1") (pintype "passive"))
      (node (ref "D1") (pin "C") (pinfunction "C_C") (pintype "passive"))
      (node (ref "D2") (pin "C") (pinfunction "C_C") (pintype "passive"))
      (node (ref "D3") (pin "C") (pinfunction "C_C") (pintype "passive"))
      (node (ref "D4") (pin "C") (pinfunction "C_C") (pintype "passive"))
      (node (ref "D5") (pin "C") (pinfunction "C_C") (pintype "passive"))
      (node (ref "D6") (pin "C") (pinfunction "C_C") (pintype "passive"))
      (node (ref "D7") (pin "C") (pinfunction "C_C") (pintype "passive"))
      (node (ref "D8") (pin "C") (pinfunction "C_C") (pintype "passive"))
      (node (ref "IC1") (pin "2") (pinfunction "IN_2") (pintype "bidirectional"))
      (node (ref "IC2") (pin "2") (pinfunction "IN_2") (pintype "bidirectional"))
      (node (ref "IC3") (pin "10") (pinfunction "COM_10") (pintype "bidirectional"))
      (node (ref "K1") (pin "8") (pinfunction "8_8") (pintype "passive"))
      (node (ref "K2") (pin "8") (pinfunction "8_8") (pintype "passive"))
      (node (ref "K3") (pin "8") (pinfunction "8_8") (pintype "passive"))
      (node (ref "K4") (pin "8") (pinfunction "8_8") (pintype "passive"))
      (node (ref "K5") (pin "8") (pinfunction "8_8") (pintype "passive"))
      (node (ref "K6") (pin "8") (pinfunction "8_8") (pintype "passive"))
      (node (ref "K7") (pin "8") (pinfunction "8_8") (pintype "passive"))
      (node (ref "K8") (pin "8") (pinfunction "8_8") (pintype "passive"))
      (node (ref "R1") (pin "1") (pinfunction "1_1") (pintype "passive"))
      (node (ref "R15") (pin "1") (pinfunction "1_1") (pintype "passive"))
      (node (ref "R16") (pin "1") (pinfunction "1_1") (pintype "passive"))
      (node (ref "R2") (pin "1") (pinfunction "1_1") (pintype "passive"))
      (node (ref "R94") (pin "2") (pinfunction "2_2") (pintype "passive"))
    )
    (net (code "5") (name "+12V_MEA") (class "Default")
      (node (ref "J1") (pin "13") (pinfunction "13_13") (pintype "bidirectional"))
      (node (ref "R94") (pin "1") (pinfunction "1_1") (pintype "passive"))
      (node (ref "R95") (pin "2") (pinfunction "2_2") (pintype "passive"))
    )
    (net (code "6") (name "AC_L") (class "Default")
      (node (ref "AC/DC1") (pin "AC_L") (pinfunction "AC/L_AC_L") (pintype "input"))
      (node (ref "AC_L") (pin "1") (pinfunction "KL_1") (pintype "passive"))
      (node (ref "AC_L") (pin "2") (pinfunction "KL_2") (pintype "passive"))
      (node (ref "C21") (pin "1") (pinfunction "1_1") (pintype "passive"))
      (node (ref "K1") (pin "3") (pinfunction "3_3") (pintype "passive"))
      (node (ref "K1") (pin "6") (pinfunction "6_6") (pintype "passive"))
      (node (ref "K2") (pin "3") (pinfunction "3_3") (pintype "passive"))
      (node (ref "K2") (pin "6") (pinfunction "6_6") (pintype "passive"))
      (node (ref "K3") (pin "3") (pinfunction "3_3") (pintype "passive"))
      (node (ref "K3") (pin "6") (pinfunction "6_6") (pintype "passive"))
      (node (ref "K4") (pin "3") (pinfunction "3_3") (pintype "passive"))
      (node (ref "K4") (pin "6") (pinfunction "6_6") (pintype "passive"))
      (node (ref "K5") (pin "3") (pinfunction "3_3") (pintype "passive"))
      (node (ref "K5") (pin "6") (pinfunction "6_6") (pintype "passive"))
      (node (ref "K6") (pin "3") (pinfunction "3_3") (pintype "passive"))
      (node (ref "K6") (pin "6") (pinfunction "6_6") (pintype "passive"))
      (node (ref "K7") (pin "3") (pinfunction "3_3") (pintype "passive"))
      (node (ref "K7") (pin "6") (pinfunction "6_6") (pintype "passive"))
      (node (ref "K8") (pin "3") (pinfunction "3_3") (pintype "passive"))
      (node (ref "K8") (pin "6") (pinfunction "6_6") (pintype "passive"))
      (node (ref "R60") (pin "1") (pinfunction "1_1") (pintype "passive"))
    )
    (net (code "7") (name "AC_N") (class "Default")
      (node (ref "AC/DC1") (pin "AC_N") (pinfunction "AC/N_AC_N") (pintype "input"))
      (node (ref "AC_N") (pin "1") (pinfunction "KL_1") (pintype "passive"))
      (node (ref "AC_N") (pin "2") (pinfunction "KL_2") (pintype "passive"))
      (node (ref "R57") (pin "1") (pinfunction "1_1") (pintype "passive"))
      (node (ref "R58") (pin "1") (pinfunction "1_1") (pintype "passive"))
      (node (ref "R59") (pin "1") (pinfunction "1_1") (pintype "passive"))
    )
    (net (code "8") (name "AGND") (class "Default")
      (node (ref "C22") (pin "2") (pinfunction "2_2") (pintype "passive"))
      (node (ref "C23") (pin "2") (pinfunction "2_2") (pintype "passive"))
      (node (ref "C24") (pin "2") (pinfunction "2_2") (pintype "passive"))
      (node (ref "C25") (pin "2") (pinfunction "2_2") (pintype "passive"))
      (node (ref "C26") (pin "2") (pinfunction "2_2") (pintype "passive"))
      (node (ref "C27") (pin "2") (pinfunction "2_2") (pintype "passive"))
      (node (ref "C28") (pin "2") (pinfunction "2_2") (pintype "passive"))
      (node (ref "C29") (pin "2") (pinfunction "2_2") (pintype "passive"))
      (node (ref "C30") (pin "2") (pinfunction "2_2") (pintype "passive"))
      (node (ref "C31") (pin "2") (pinfunction "2_2") (pintype "passive"))
      (node (ref "C32") (pin "2") (pinfunction "2_2") (pintype "passive"))
      (node (ref "C36") (pin "2") (pinfunction "2_2") (pintype "passive"))
      (node (ref "C37") (pin "2") (pinfunction "2_2") (pintype "passive"))
      (node (ref "C38") (pin "2") (pinfunction "2_2") (pintype "passive"))
      (node (ref "C39") (pin "2") (pinfunction "2_2") (pintype "passive"))
      (node (ref "C40") (pin "2") (pinfunction "2_2") (pintype "passive"))
      (node (ref "C41") (pin "2") (pinfunction "2_2") (pintype "passive"))
      (node (ref "C42") (pin "2") (pinfunction "2_2") (pintype "passive"))
      (node (ref "C43") (pin "2") (pinfunction "2_2") (pintype "passive"))
      (node (ref "C44") (pin "2") (pinfunction "2_2") (pintype "passive"))
      (node (ref "C48") (pin "2") (pinfunction "2_2") (pintype "passive"))
      (node (ref "C49") (pin "2") (pinfunction "2_2") (pintype "passive"))
      (node (ref "C5") (pin "2") (pinfunction "2_2") (pintype "passive"))
      (node (ref "C50") (pin "2") (pinfunction "2_2") (pintype "passive"))
      (node (ref "C54") (pin "2") (pinfunction "2_2") (pintype "passive"))
      (node (ref "C55") (pin "2") (pinfunction "2_2") (pintype "passive"))
      (node (ref "C56") (pin "2") (pinfunction "2_2") (pintype "passive"))
      (node (ref "D10") (pin "A") (pinfunction "A_A") (pintype "passive"))
      (node (ref "D11") (pin "A") (pinfunction "A_A") (pintype "passive"))
      (node (ref "IC10") (pin "5") (pinfunction "GND_5") (pintype "power_in"))
      (node (ref "IC11") (pin "5") (pinfunction "GND_5") (pintype "power_in"))
      (node (ref "IC12") (pin "5") (pinfunction "GND_5") (pintype "power_in"))
      (node (ref "IC14") (pin "5") (pinfunction "GND_5") (pintype "power_in"))
      (node (ref "IC16") (pin "5") (pinfunction "GND_5") (pintype "power_in"))
      (node (ref "IC5") (pin "4") (pinfunction "GND_4") (pintype "power_in"))
      (node (ref "IC6") (pin "5") (pinfunction "GND_5") (pintype "power_in"))
      (node (ref "IC7") (pin "5") (pinfunction "GND_5") (pintype "power_in"))
      (node (ref "IC8") (pin "5") (pinfunction "GND_5") (pintype "power_in"))
      (node (ref "R104") (pin "2") (pinfunction "2_2") (pintype "passive"))
      (node (ref "R120") (pin "2") (pinfunction "2_2") (pintype "passive"))
      (node (ref "R40") (pin "2") (pinfunction "2_2") (pintype "passive"))
      (node (ref "R48") (pin "2") (pinfunction "2_2") (pintype "passive"))
      (node (ref "R56") (pin "2") (pinfunction "2_2") (pintype "passive"))
      (node (ref "R57") (pin "2") (pinfunction "2_2") (pintype "passive"))
      (node (ref "R58") (pin "2") (pinfunction "2_2") (pintype "passive"))
      (node (ref "R59") (pin "2") (pinfunction "2_2") (pintype "passive"))
      (node (ref "R72") (pin "2") (pinfunction "2_2") (pintype "passive"))
      (node (ref "R80") (pin "2") (pinfunction "2_2") (pintype "passive"))
      (node (ref "R88") (pin "2") (pinfunction "2_2") (pintype "passive"))
    )
    (net (code "9") (name "C13_IN1") (class "Default")
      (node (ref "R25") (pin "2") (pinfunction "2_2") (pintype "passive"))
      (node (ref "R33") (pin "1") (pinfunction "1_1") (pintype "passive"))
      (node (ref "R35") (pin "2") (pinfunction "2_2") (pintype "passive"))
    )
    (net (code "10") (name "C13_IN2") (class "Default")
      (node (ref "R32") (pin "2") (pinfunction "2_2") (pintype "passive"))
      (node (ref "R49") (pin "1") (pinfunction "1_1") (pintype "passive"))
      (node (ref "R51") (pin "2") (pinfunction "2_2") (pintype "passive"))
    )
    (net (code "11") (name "C13_IN3") (class "Default")
      (node (ref "R31") (pin "2") (pinfunction "2_2") (pintype "passive"))
      (node (ref "R65") (pin "1") (pinfunction "1_1") (pintype "passive"))
      (node (ref "R67") (pin "2") (pinfunction "2_2") (pintype "passive"))
    )
    (net (code "12") (name "C13_IN4") (class "Default")
      (node (ref "R30") (pin "2") (pinfunction "2_2") (pintype "passive"))
      (node (ref "R81") (pin "1") (pinfunction "1_1") (pintype "passive"))
      (node (ref "R83") (pin "2") (pinfunction "2_2") (pintype "passive"))
    )
    (net (code "13") (name "C13_IN5") (class "Default")
      (node (ref "R26") (pin "2") (pinfunction "2_2") (pintype "passive"))
      (node (ref "R41") (pin "1") (pinfunction "1_1") (pintype "passive"))
      (node (ref "R43") (pin "2") (pinfunction "2_2") (pintype "passive"))
    )
    (net (code "14") (name "C13_IN6") (class "Default")
      (node (ref "R27") (pin "2") (pinfunction "2_2") (pintype "passive"))
      (node (ref "R73") (pin "1") (pinfunction "1_1") (pintype "passive"))
      (node (ref "R75") (pin "2") (pinfunction "2_2") (pintype "passive"))
    )
    (net (code "15") (name "C13_IN7") (class "Default")
      (node (ref "R28") (pin "2") (pinfunction "2_2") (pintype "passive"))
      (node (ref "R97") (pin "1") (pinfunction "1_1") (pintype "passive"))
      (node (ref "R99") (pin "2") (pinfunction "2_2") (pintype "passive"))
    )
    (net (code "16") (name "C13_IN8") (class "Default")
      (node (ref "R113") (pin "1") (pinfunction "1_1") (pintype "passive"))
      (node (ref "R115") (pin "2") (pinfunction "2_2") (pintype "passive"))
      (node (ref "R29") (pin "2") (pinfunction "2_2") (pintype "passive"))
    )
    (net (code "17") (name "GND") (class "Default")
      (node (ref "AC/DC1") (pin "-V") (pinfunction "-V_-V") (pintype "output"))
      (node (ref "C1") (pin "2") (pinfunction "2_2") (pintype "passive"))
      (node (ref "C10") (pin "2") (pinfunction "2_2") (pintype "passive"))
      (node (ref "C13") (pin "2") (pinfunction "2_2") (pintype "passive"))
      (node (ref "C14") (pin "2") (pinfunction "2_2") (pintype "passive"))
      (node (ref "C15") (pin "2") (pinfunction "2_2") (pintype "passive"))
      (node (ref "C16") (pin "2") (pinfunction "2_2") (pintype "passive"))
      (node (ref "C17") (pin "2") (pinfunction "2_2") (pintype "passive"))
      (node (ref "C18") (pin "2") (pinfunction "2_2") (pintype "passive"))
      (node (ref "C19") (pin "2") (pinfunction "2_2") (pintype "passive"))
      (node (ref "C2") (pin "2") (pinfunction "2_2") (pintype "passive"))
      (node (ref "C20") (pin "2") (pinfunction "2_2") (pintype "passive"))
      (node (ref "C3") (pin "2") (pinfunction "2_2") (pintype "passive"))
      (node (ref "C33") (pin "2") (pinfunction "2_2") (pintype "passive"))
      (node (ref "C34") (pin "2") (pinfunction "2_2") (pintype "passive"))
      (node (ref "C4") (pin "2") (pinfunction "2_2") (pintype "passive"))
      (node (ref "C6") (pin "2") (pinfunction "2_2") (pintype "passive"))
      (node (ref "C7") (pin "2") (pinfunction "2_2") (pintype "passive"))
      (node (ref "GND") (pin "TP") (pinfunction "P$1_TP") (pintype "bidirectional"))
      (node (ref "GND-3") (pin "TP") (pinfunction "P$1_TP") (pintype "bidirectional"))
      (node (ref "GND-5") (pin "TP") (pinfunction "P$1_TP") (pintype "bidirectional"))
      (node (ref "IC1") (pin "4") (pinfunction "GND_4") (pintype "bidirectional"))
      (node (ref "IC2") (pin "4") (pinfunction "GND_4") (pintype "bidirectional"))
      (node (ref "IC3") (pin "9") (pinfunction "GND_9") (pintype "bidirectional"))
      (node (ref "IC4") (pin "11") (pinfunction "A0_11") (pintype "bidirectional"))
      (node (ref "IC4") (pin "12") (pinfunction "A1_12") (pintype "bidirectional"))
      (node (ref "IC4") (pin "13") (pinfunction "A2_13") (pintype "bidirectional"))
      (node (ref "IC4") (pin "6") (pinfunction "VSS_6") (pintype "bidirectional"))
      (node (ref "IC4") (pin "PAD") (pinfunction "VSS_PAD") (pintype "bidirectional"))
      (node (ref "IC9") (pin "8") (pinfunction "GND_8") (pintype "power_in"))
      (node (ref "J1") (pin "12") (pinfunction "12_12") (pintype "bidirectional"))
      (node (ref "J1") (pin "14") (pinfunction "14_14") (pintype "bidirectional"))
      (node (ref "J1") (pin "16") (pinfunction "16_16") (pintype "bidirectional"))
      (node (ref "J1") (pin "9") (pinfunction "9_9") (pintype "bidirectional"))
      (node (ref "J1") (pin "Z1") (pinfunction "Z1_Z1") (pintype "bidirectional"))
      (node (ref "J1") (pin "Z2") (pinfunction "Z2_Z2") (pintype "bidirectional"))
      (node (ref "J1") (pin "Z3") (pinfunction "Z3_Z3") (pintype "bidirectional"))
      (node (ref "J1") (pin "Z4") (pinfunction "Z4_Z4") (pintype "bidirectional"))
      (node (ref "OPT1") (pin "11") (pinfunction "11_11") (pintype "passive"))
      (node (ref "OPT1") (pin "13") (pinfunction "13_13") (pintype "passive"))
      (node (ref "OPT1") (pin "15") (pinfunction "15_15") (pintype "passive"))
      (node (ref "OPT1") (pin "9") (pinfunction "9_9") (pintype "passive"))
      (node (ref "OPT2") (pin "11") (pinfunction "11_11") (pintype "passive"))
      (node (ref "OPT2") (pin "13") (pinfunction "13_13") (pintype "passive"))
      (node (ref "OPT2") (pin "15") (pinfunction "15_15") (pintype "passive"))
      (node (ref "OPT2") (pin "9") (pinfunction "9_9") (pintype "passive"))
      (node (ref "R12") (pin "2") (pinfunction "2_2") (pintype "passive"))
      (node (ref "R14") (pin "2") (pinfunction "2_2") (pintype "passive"))
      (node (ref "R4") (pin "2") (pinfunction "2_2") (pintype "passive"))
      (node (ref "R6") (pin "2") (pinfunction "2_2") (pintype "passive"))
      (node (ref "R95") (pin "1") (pinfunction "1_1") (pintype "passive"))
      (node (ref "Z1") (pin "A") (pinfunction "A_A") (pintype "passive"))
    )
    (net (code "18") (name "I2C_SCL") (class "Default")
      (node (ref "IC4") (pin "8") (pinfunction "SCL_8") (pintype "bidirectional"))
      (node (ref "J1") (pin "8") (pinfunction "8_8") (pintype "bidirectional"))
    )
    (net (code "19") (name "I2C_SDA") (class "Default")
      (node (ref "IC4") (pin "9") (pinfunction "SDA_9") (pintype "bidirectional"))
      (node (ref "J1") (pin "7") (pinfunction "7_7") (pintype "bidirectional"))
    )
    (net (code "20") (name "MCP_REL_RST") (class "Default")
      (node (ref "IC4") (pin "14") (pinfunction "~{RESET}_14") (pintype "bidirectional"))
      (node (ref "J1") (pin "15") (pinfunction "15_15") (pintype "bidirectional"))
    )
    (net (code "21") (name "MUX_A") (class "Default")
      (node (ref "IC4") (pin "25") (pinfunction "IO2.0_25") (pintype "bidirectional"))
      (node (ref "IC9") (pin "11") (pinfunction "A_11") (pintype "input"))
      (node (ref "R93") (pin "4") (pinfunction "4_4") (pintype "passive"))
    )
    (net (code "22") (name "MUX_B") (class "Default")
      (node (ref "IC4") (pin "26") (pinfunction "IO2.1_26") (pintype "bidirectional"))
      (node (ref "IC9") (pin "10") (pinfunction "B_10") (pintype "input"))
      (node (ref "R93") (pin "3") (pinfunction "3_3") (pintype "passive"))
    )
    (net (code "23") (name "MUX_C") (class "Default")
      (node (ref "IC4") (pin "27") (pinfunction "IO2.2_27") (pintype "bidirectional"))
      (node (ref "IC9") (pin "9") (pinfunction "C_9") (pintype "input"))
      (node (ref "R93") (pin "2") (pinfunction "2_2") (pintype "passive"))
    )
    (net (code "24") (name "MUX_EN") (class "Default")
      (node (ref "IC4") (pin "28") (pinfunction "IO2.3_28") (pintype "bidirectional"))
      (node (ref "IC9") (pin "7") (pinfunction "~{EN}_7") (pintype "input"))
      (node (ref "R93") (pin "1") (pinfunction "1_1") (pintype "passive"))
    )
    (net (code "25") (name "Net-(3VFB-P$1)") (class "Default")
      (node (ref "3VFB") (pin "TP") (pinfunction "P$1_TP") (pintype "bidirectional"))
      (node (ref "C12") (pin "2") (pinfunction "2_2") (pintype "passive"))
      (node (ref "R10") (pin "2") (pinfunction "2_2") (pintype "passive"))
      (node (ref "R13") (pin "2") (pinfunction "2_2") (pintype "passive"))
      (node (ref "R14") (pin "1") (pinfunction "1_1") (pintype "passive"))
    )
    (net (code "26") (name "Net-(5VFB-P$1)") (class "Default")
      (node (ref "5VFB") (pin "TP") (pinfunction "P$1_TP") (pintype "bidirectional"))
      (node (ref "C11") (pin "2") (pinfunction "2_2") (pintype "passive"))
      (node (ref "R11") (pin "2") (pinfunction "2_2") (pintype "passive"))
      (node (ref "R12") (pin "1") (pinfunction "1_1") (pintype "passive"))
      (node (ref "R8") (pin "2") (pinfunction "2_2") (pintype "passive"))
    )
    (net (code "27") (name "Net-(12VDC-P$1)") (class "Default")
      (node (ref "12VDC") (pin "TP") (pinfunction "P$1_TP") (pintype "bidirectional"))
      (node (ref "AC/DC1") (pin "+V") (pinfunction "+V_+V") (pintype "output"))
      (node (ref "C10") (pin "1") (pinfunction "1_1") (pintype "passive"))
      (node (ref "C13") (pin "1") (pinfunction "1_1") (pintype "passive"))
      (node (ref "C16") (pin "1") (pinfunction "1_1") (pintype "passive"))
      (node (ref "R15") (pin "2") (pinfunction "2_2") (pintype "passive"))
      (node (ref "R16") (pin "2") (pinfunction "2_2") (pintype "passive"))
      (node (ref "Z1") (pin "C") (pinfunction "C_C") (pintype "passive"))
    )
    (net (code "28") (name "Net-(C8-Pad1)") (class "Default")
      (node (ref "C8") (pin "1") (pinfunction "1_1") (pintype "passive"))
      (node (ref "R7") (pin "1") (pinfunction "1_1") (pintype "passive"))
    )
    (net (code "29") (name "Net-(C9-Pad1)") (class "Default")
      (node (ref "C9") (pin "1") (pinfunction "1_1") (pintype "passive"))
      (node (ref "R9") (pin "1") (pinfunction "1_1") (pintype "passive"))
    )
    (net (code "30") (name "Net-(C21-Pad2)") (class "Default")
      (node (ref "C21") (pin "2") (pinfunction "2_2") (pintype "passive"))
      (node (ref "R60") (pin "2") (pinfunction "2_2") (pintype "passive"))
      (node (ref "R61") (pin "1") (pinfunction "1_1") (pintype "passive"))
    )
    (net (code "31") (name "Net-(D10-PadC)") (class "Default")
      (node (ref "D10") (pin "C") (pinfunction "C_C") (pintype "passive"))
      (node (ref "D9") (pin "A") (pinfunction "A_A") (pintype "passive"))
      (node (ref "R61") (pin "2") (pinfunction "2_2") (pintype "passive"))
    )
    (net (code "32") (name "Net-(D11-PadC)") (class "Default")
      (node (ref "D11") (pin "C") (pinfunction "C_C") (pintype "passive"))
      (node (ref "D9") (pin "C") (pinfunction "C_C") (pintype "passive"))
      (node (ref "R62") (pin "1") (pinfunction "1_1") (pintype "passive"))
    )
    (net (code "33") (name "Net-(IC1-AAM)") (class "Default")
      (node (ref "IC1") (pin "1") (pinfunction "AAM_1") (pintype "bidirectional"))
      (node (ref "R3") (pin "2") (pinfunction "2_2") (pintype "passive"))
      (node (ref "R4") (pin "1") (pinfunction "1_1") (pintype "passive"))
    )
    (net (code "34") (name "Net-(IC1-BST)") (class "Default")
      (node (ref "IC1") (pin "5") (pinfunction "BST_5") (pintype "bidirectional"))
      (node (ref "R7") (pin "2") (pinfunction "2_2") (pintype "passive"))
    )
    (net (code "35") (name "Net-(IC1-EN)") (class "Default")
      (node (ref "IC1") (pin "6") (pinfunction "EN_6") (pintype "bidirectional"))
      (node (ref "R1") (pin "2") (pinfunction "2_2") (pintype "passive"))
    )
    (net (code "36") (name "Net-(IC1-FB)") (class "Default")
      (node (ref "IC1") (pin "8") (pinfunction "FB_8") (pintype "bidirectional"))
      (node (ref "R8") (pin "1") (pinfunction "1_1") (pintype "passive"))
    )
    (net (code "37") (name "Net-(IC1-SW)") (class "Default")
      (node (ref "C8") (pin "2") (pinfunction "2_2") (pintype "passive"))
      (node (ref "IC1") (pin "3") (pinfunction "SW_3") (pintype "bidirectional"))
      (node (ref "L1") (pin "1") (pinfunction "1_1") (pintype "passive"))
      (node (ref "SW") (pin "TP") (pinfunction "P$1_TP") (pintype "bidirectional"))
    )
    (net (code "38") (name "Net-(IC1-VCC)") (class "Default")
      (node (ref "C6") (pin "1") (pinfunction "1_1") (pintype "passive"))
      (node (ref "IC1") (pin "7") (pinfunction "VCC_7") (pintype "bidirectional"))
      (node (ref "R3") (pin "1") (pinfunction "1_1") (pintype "passive"))
    )
    (net (code "39") (name "Net-(IC2-AAM)") (class "Default")
      (node (ref "IC2") (pin "1") (pinfunction "AAM_1") (pintype "bidirectional"))
      (node (ref "R5") (pin "2") (pinfunction "2_2") (pintype "passive"))
      (node (ref "R6") (pin "1") (pinfunction "1_1") (pintype "passive"))
    )
    (net (code "40") (name "Net-(IC2-BST)") (class "Default")
      (node (ref "IC2") (pin "5") (pinfunction "BST_5") (pintype "bidirectional"))
      (node (ref "R9") (pin "2") (pinfunction "2_2") (pintype "passive"))
    )
    (net (code "41") (name "Net-(IC2-EN)") (class "Default")
      (node (ref "IC2") (pin "6") (pinfunction "EN_6") (pintype "bidirectional"))
      (node (ref "R2") (pin "2") (pinfunction "2_2") (pintype "passive"))
    )
    (net (code "42") (name "Net-(IC2-FB)") (class "Default")
      (node (ref "IC2") (pin "8") (pinfunction "FB_8") (pintype "bidirectional"))
      (node (ref "R10") (pin "1") (pinfunction "1_1") (pintype "passive"))
    )
    (net (code "43") (name "Net-(IC2-SW)") (class "Default")
      (node (ref "C9") (pin "2") (pinfunction "2_2") (pintype "passive"))
      (node (ref "IC2") (pin "3") (pinfunction "SW_3") (pintype "bidirectional"))
      (node (ref "L2") (pin "1") (pinfunction "1_1") (pintype "passive"))
      (node (ref "SW3") (pin "TP") (pinfunction "P$1_TP") (pintype "bidirectional"))
    )
    (net (code "44") (name "Net-(IC2-VCC)") (class "Default")
      (node (ref "C7") (pin "1") (pinfunction "1_1") (pintype "passive"))
      (node (ref "IC2") (pin "7") (pinfunction "VCC_7") (pintype "bidirectional"))
      (node (ref "R5") (pin "1") (pinfunction "1_1") (pintype "passive"))
    )
    (net (code "45") (name "Net-(IC3-1C)") (class "Default")
      (node (ref "IC3") (pin "18") (pinfunction "1C_18") (pintype "bidirectional"))
      (node (ref "R17") (pin "1") (pinfunction "1_1") (pintype "passive"))
    )
    (net (code "46") (name "Net-(IC3-2C)") (class "Default")
      (node (ref "IC3") (pin "17") (pinfunction "2C_17") (pintype "bidirectional"))
      (node (ref "R18") (pin "1") (pinfunction "1_1") (pintype "passive"))
    )
    (net (code "47") (name "Net-(IC3-3C)") (class "Default")
      (node (ref "IC3") (pin "16") (pinfunction "3C_16") (pintype "bidirectional"))
      (node (ref "R19") (pin "1") (pinfunction "1_1") (pintype "passive"))
    )
    (net (code "48") (name "Net-(IC3-4C)") (class "Default")
      (node (ref "IC3") (pin "15") (pinfunction "4C_15") (pintype "bidirectional"))
      (node (ref "R20") (pin "1") (pinfunction "1_1") (pintype "passive"))
    )
    (net (code "49") (name "Net-(IC3-5C)") (class "Default")
      (node (ref "IC3") (pin "14") (pinfunction "5C_14") (pintype "bidirectional"))
      (node (ref "R21") (pin "1") (pinfunction "1_1") (pintype "passive"))
    )
    (net (code "50") (name "Net-(IC3-6C)") (class "Default")
      (node (ref "IC3") (pin "13") (pinfunction "6C_13") (pintype "bidirectional"))
      (node (ref "R22") (pin "1") (pinfunction "1_1") (pintype "passive"))
    )
    (net (code "51") (name "Net-(IC3-7C)") (class "Default")
      (node (ref "IC3") (pin "12") (pinfunction "7C_12") (pintype "bidirectional"))
      (node (ref "R23") (pin "1") (pinfunction "1_1") (pintype "passive"))
    )
    (net (code "52") (name "Net-(IC3-8C)") (class "Default")
      (node (ref "IC3") (pin "11") (pinfunction "8C_11") (pintype "bidirectional"))
      (node (ref "R24") (pin "1") (pinfunction "1_1") (pintype "passive"))
    )
    (net (code "53") (name "Net-(IC5-VIN)") (class "Default")
      (node (ref "C22") (pin "1") (pinfunction "1_1") (pintype "passive"))
      (node (ref "IC5") (pin "1") (pinfunction "VIN_1") (pintype "power_in"))
      (node (ref "R62") (pin "2") (pinfunction "2_2") (pintype "passive"))
    )
    (net (code "54") (name "Net-(IC6-INN)") (class "Default")
      (node (ref "C25") (pin "1") (pinfunction "1_1") (pintype "passive"))
      (node (ref "IC6") (pin "3") (pinfunction "INN_3") (pintype "input"))
      (node (ref "R34") (pin "2") (pinfunction "2_2") (pintype "passive"))
    )
    (net (code "55") (name "Net-(IC6-INP)") (class "Default")
      (node (ref "C24") (pin "1") (pinfunction "1_1") (pintype "passive"))
      (node (ref "IC6") (pin "2") (pinfunction "INP_2") (pintype "input"))
      (node (ref "R33") (pin "2") (pinfunction "2_2") (pintype "passive"))
    )
    (net (code "56") (name "Net-(IC6-VP)") (class "Default")
      (node (ref "C26") (pin "1") (pinfunction "1_1") (pintype "passive"))
      (node (ref "IC6") (pin "4") (pinfunction "VP_4") (pintype "input"))
      (node (ref "R39") (pin "2") (pinfunction "2_2") (pintype "passive"))
      (node (ref "R40") (pin "1") (pinfunction "1_1") (pintype "passive"))
    )
    (net (code "57") (name "Net-(IC7-INN)") (class "Default")
      (node (ref "C28") (pin "1") (pinfunction "1_1") (pintype "passive"))
      (node (ref "IC7") (pin "3") (pinfunction "INN_3") (pintype "input"))
      (node (ref "R42") (pin "2") (pinfunction "2_2") (pintype "passive"))
    )
    (net (code "58") (name "Net-(IC7-INP)") (class "Default")
      (node (ref "C27") (pin "1") (pinfunction "1_1") (pintype "passive"))
      (node (ref "IC7") (pin "2") (pinfunction "INP_2") (pintype "input"))
      (node (ref "R41") (pin "2") (pinfunction "2_2") (pintype "passive"))
    )
    (net (code "59") (name "Net-(IC7-VP)") (class "Default")
      (node (ref "C29") (pin "1") (pinfunction "1_1") (pintype "passive"))
      (node (ref "IC7") (pin "4") (pinfunction "VP_4") (pintype "input"))
      (node (ref "R47") (pin "2") (pinfunction "2_2") (pintype "passive"))
      (node (ref "R48") (pin "1") (pinfunction "1_1") (pintype "passive"))
    )
    (net (code "60") (name "Net-(IC8-INN)") (class "Default")
      (node (ref "C31") (pin "1") (pinfunction "1_1") (pintype "passive"))
      (node (ref "IC8") (pin "3") (pinfunction "INN_3") (pintype "input"))
      (node (ref "R50") (pin "2") (pinfunction "2_2") (pintype "passive"))
    )
    (net (code "61") (name "Net-(IC8-INP)") (class "Default")
      (node (ref "C30") (pin "1") (pinfunction "1_1") (pintype "passive"))
      (node (ref "IC8") (pin "2") (pinfunction "INP_2") (pintype "input"))
      (node (ref "R49") (pin "2") (pinfunction "2_2") (pintype "passive"))
    )
    (net (code "62") (name "Net-(IC8-VP)") (class "Default")
      (node (ref "C32") (pin "1") (pinfunction "1_1") (pintype "passive"))
      (node (ref "IC8") (pin "4") (pinfunction "VP_4") (pintype "input"))
      (node (ref "R55") (pin "2") (pinfunction "2_2") (pintype "passive"))
      (node (ref "R56") (pin "1") (pinfunction "1_1") (pintype "passive"))
    )
    (net (code "63") (name "Net-(IC9-Y)") (class "Default")
      (node (ref "IC9") (pin "5") (pinfunction "Y_5") (pintype "bidirectional"))
      (node (ref "R91") (pin "1") (pinfunction "1_1") (pintype "passive"))
    )
    (net (code "64") (name "Net-(IC9-~{Y})") (class "Default")
      (node (ref "IC9") (pin "6") (pinfunction "~{Y}_6") (pintype "bidirectional"))
      (node (ref "R92") (pin "1") (pinfunction "1_1") (pintype "passive"))
    )
    (net (code "65") (name "Net-(IC10-INN)") (class "Default")
      (node (ref "C37") (pin "1") (pinfunction "1_1") (pintype "passive"))
      (node (ref "IC10") (pin "3") (pinfunction "INN_3") (pintype "input"))
      (node (ref "R66") (pin "2") (pinfunction "2_2") (pintype "passive"))
    )
    (net (code "66") (name "Net-(IC10-INP)") (class "Default")
      (node (ref "C36") (pin "1") (pinfunction "1_1") (pintype "passive"))
      (node (ref "IC10") (pin "2") (pinfunction "INP_2") (pintype "input"))
      (node (ref "R65") (pin "2") (pinfunction "2_2") (pintype "passive"))
    )
    (net (code "67") (name "Net-(IC10-VP)") (class "Default")
      (node (ref "C38") (pin "1") (pinfunction "1_1") (pintype "passive"))
      (node (ref "IC10") (pin "4") (pinfunction "VP_4") (pintype "input"))
      (node (ref "R71") (pin "2") (pinfunction "2_2") (pintype "passive"))
      (node (ref "R72") (pin "1") (pinfunction "1_1") (pintype "passive"))
    )
    (net (code "68") (name "Net-(IC11-INN)") (class "Default")
      (node (ref "C40") (pin "1") (pinfunction "1_1") (pintype "passive"))
      (node (ref "IC11") (pin "3") (pinfunction "INN_3") (pintype "input"))
      (node (ref "R74") (pin "2") (pinfunction "2_2") (pintype "passive"))
    )
    (net (code "69") (name "Net-(IC11-INP)") (class "Default")
      (node (ref "C39") (pin "1") (pinfunction "1_1") (pintype "passive"))
      (node (ref "IC11") (pin "2") (pinfunction "INP_2") (pintype "input"))
      (node (ref "R73") (pin "2") (pinfunction "2_2") (pintype "passive"))
    )
    (net (code "70") (name "Net-(IC11-VP)") (class "Default")
      (node (ref "C41") (pin "1") (pinfunction "1_1") (pintype "passive"))
      (node (ref "IC11") (pin "4") (pinfunction "VP_4") (pintype "input"))
      (node (ref "R79") (pin "2") (pinfunction "2_2") (pintype "passive"))
      (node (ref "R80") (pin "1") (pinfunction "1_1") (pintype "passive"))
    )
    (net (code "71") (name "Net-(IC12-INN)") (class "Default")
      (node (ref "C43") (pin "1") (pinfunction "1_1") (pintype "passive"))
      (node (ref "IC12") (pin "3") (pinfunction "INN_3") (pintype "input"))
      (node (ref "R82") (pin "2") (pinfunction "2_2") (pintype "passive"))
    )
    (net (code "72") (name "Net-(IC12-INP)") (class "Default")
      (node (ref "C42") (pin "1") (pinfunction "1_1") (pintype "passive"))
      (node (ref "IC12") (pin "2") (pinfunction "INP_2") (pintype "input"))
      (node (ref "R81") (pin "2") (pinfunction "2_2") (pintype "passive"))
    )
    (net (code "73") (name "Net-(IC12-VP)") (class "Default")
      (node (ref "C44") (pin "1") (pinfunction "1_1") (pintype "passive"))
      (node (ref "IC12") (pin "4") (pinfunction "VP_4") (pintype "input"))
      (node (ref "R87") (pin "2") (pinfunction "2_2") (pintype "passive"))
      (node (ref "R88") (pin "1") (pinfunction "1_1") (pintype "passive"))
    )
    (net (code "74") (name "Net-(IC14-INN)") (class "Default")
      (node (ref "C49") (pin "1") (pinfunction "1_1") (pintype "passive"))
      (node (ref "IC14") (pin "3") (pinfunction "INN_3") (pintype "input"))
      (node (ref "R98") (pin "2") (pinfunction "2_2") (pintype "passive"))
    )
    (net (code "75") (name "Net-(IC14-INP)") (class "Default")
      (node (ref "C48") (pin "1") (pinfunction "1_1") (pintype "passive"))
      (node (ref "IC14") (pin "2") (pinfunction "INP_2") (pintype "input"))
      (node (ref "R97") (pin "2") (pinfunction "2_2") (pintype "passive"))
    )
    (net (code "76") (name "Net-(IC14-VP)") (class "Default")
      (node (ref "C50") (pin "1") (pinfunction "1_1") (pintype "passive"))
      (node (ref "IC14") (pin "4") (pinfunction "VP_4") (pintype "input"))
      (node (ref "R103") (pin "2") (pinfunction "2_2") (pintype "passive"))
      (node (ref "R104") (pin "1") (pinfunction "1_1") (pintype "passive"))
    )
    (net (code "77") (name "Net-(IC16-INN)") (class "Default")
      (node (ref "C55") (pin "1") (pinfunction "1_1") (pintype "passive"))
      (node (ref "IC16") (pin "3") (pinfunction "INN_3") (pintype "input"))
      (node (ref "R114") (pin "2") (pinfunction "2_2") (pintype "passive"))
    )
    (net (code "78") (name "Net-(IC16-INP)") (class "Default")
      (node (ref "C54") (pin "1") (pinfunction "1_1") (pintype "passive"))
      (node (ref "IC16") (pin "2") (pinfunction "INP_2") (pintype "input"))
      (node (ref "R113") (pin "2") (pinfunction "2_2") (pintype "passive"))
    )
    (net (code "79") (name "Net-(IC16-VP)") (class "Default")
      (node (ref "C56") (pin "1") (pinfunction "1_1") (pintype "passive"))
      (node (ref "IC16") (pin "4") (pinfunction "VP_4") (pintype "input"))
      (node (ref "R119") (pin "2") (pinfunction "2_2") (pintype "passive"))
      (node (ref "R120") (pin "1") (pinfunction "1_1") (pintype "passive"))
    )
    (net (code "80") (name "Net-(OPT1-Pad1)") (class "Default")
      (node (ref "OPT1") (pin "1") (pinfunction "1_1") (pintype "passive"))
      (node (ref "R63") (pin "8") (pinfunction "8_8") (pintype "passive"))
    )
    (net (code "81") (name "Net-(OPT1-Pad3)") (class "Default")
      (node (ref "OPT1") (pin "3") (pinfunction "3_3") (pintype "passive"))
      (node (ref "R63") (pin "7") (pinfunction "7_7") (pintype "passive"))
    )
    (net (code "82") (name "Net-(OPT1-Pad5)") (class "Default")
      (node (ref "OPT1") (pin "5") (pinfunction "5_5") (pintype "passive"))
      (node (ref "R63") (pin "6") (pinfunction "6_6") (pintype "passive"))
    )
    (net (code "83") (name "Net-(OPT1-Pad7)") (class "Default")
      (node (ref "OPT1") (pin "7") (pinfunction "7_7") (pintype "passive"))
      (node (ref "R63") (pin "5") (pinfunction "5_5") (pintype "passive"))
    )
    (net (code "84") (name "Net-(OPT2-Pad1)") (class "Default")
      (node (ref "OPT2") (pin "1") (pinfunction "1_1") (pintype "passive"))
      (node (ref "R64") (pin "8") (pinfunction "8_8") (pintype "passive"))
    )
    (net (code "85") (name "Net-(OPT2-Pad3)") (class "Default")
      (node (ref "OPT2") (pin "3") (pinfunction "3_3") (pintype "passive"))
      (node (ref "R64") (pin "7") (pinfunction "7_7") (pintype "passive"))
    )
    (net (code "86") (name "Net-(OPT2-Pad5)") (class "Default")
      (node (ref "OPT2") (pin "5") (pinfunction "5_5") (pintype "passive"))
      (node (ref "R64") (pin "6") (pinfunction "6_6") (pintype "passive"))
    )
    (net (code "87") (name "Net-(OPT2-Pad7)") (class "Default")
      (node (ref "OPT2") (pin "7") (pinfunction "7_7") (pintype "passive"))
      (node (ref "R64") (pin "5") (pinfunction "5_5") (pintype "passive"))
    )
    (net (code "88") (name "Net-(R36-Pad2)") (class "Default")
      (node (ref "R36") (pin "2") (pinfunction "2_2") (pintype "passive"))
      (node (ref "R37") (pin "1") (pinfunction "1_1") (pintype "passive"))
    )
    (net (code "89") (name "Net-(R37-Pad2)") (class "Default")
      (node (ref "R37") (pin "2") (pinfunction "2_2") (pintype "passive"))
      (node (ref "R38") (pin "1") (pinfunction "1_1") (pintype "passive"))
    )
    (net (code "90") (name "Net-(R38-Pad2)") (class "Default")
      (node (ref "R38") (pin "2") (pinfunction "2_2") (pintype "passive"))
      (node (ref "R39") (pin "1") (pinfunction "1_1") (pintype "passive"))
    )
    (net (code "91") (name "Net-(R44-Pad2)") (class "Default")
      (node (ref "R44") (pin "2") (pinfunction "2_2") (pintype "passive"))
      (node (ref "R45") (pin "1") (pinfunction "1_1") (pintype "passive"))
    )
    (net (code "92") (name "Net-(R45-Pad2)") (class "Default")
      (node (ref "R45") (pin "2") (pinfunction "2_2") (pintype "passive"))
      (node (ref "R46") (pin "1") (pinfunction "1_1") (pintype "passive"))
    )
    (net (code "93") (name "Net-(R46-Pad2)") (class "Default")
      (node (ref "R46") (pin "2") (pinfunction "2_2") (pintype "passive"))
      (node (ref "R47") (pin "1") (pinfunction "1_1") (pintype "passive"))
    )
    (net (code "94") (name "Net-(R52-Pad2)") (class "Default")
      (node (ref "R52") (pin "2") (pinfunction "2_2") (pintype "passive"))
      (node (ref "R53") (pin "1") (pinfunction "1_1") (pintype "passive"))
    )
    (net (code "95") (name "Net-(R53-Pad2)") (class "Default")
      (node (ref "R53") (pin "2") (pinfunction "2_2") (pintype "passive"))
      (node (ref "R54") (pin "1") (pinfunction "1_1") (pintype "passive"))
    )
    (net (code "96") (name "Net-(R54-Pad2)") (class "Default")
      (node (ref "R54") (pin "2") (pinfunction "2_2") (pintype "passive"))
      (node (ref "R55") (pin "1") (pinfunction "1_1") (pintype "passive"))
    )
    (net (code "97") (name "Net-(R68-Pad2)") (class "Default")
      (node (ref "R68") (pin "2") (pinfunction "2_2") (pintype "passive"))
      (node (ref "R69") (pin "1") (pinfunction "1_1") (pintype "passive"))
    )
    (net (code "98") (name "Net-(R69-Pad2)") (class "Default")
      (node (ref "R69") (pin "2") (pinfunction "2_2") (pintype "passive"))
      (node (ref "R70") (pin "1") (pinfunction "1_1") (pintype "passive"))
    )
    (net (code "99") (name "Net-(R70-Pad2)") (class "Default")
      (node (ref "R70") (pin "2") (pinfunction "2_2") (pintype "passive"))
      (node (ref "R71") (pin "1") (pinfunction "1_1") (pintype "passive"))
    )
    (net (code "100") (name "Net-(R76-Pad2)") (class "Default")
      (node (ref "R76") (pin "2") (pinfunction "2_2") (pintype "passive"))
      (node (ref "R77") (pin "1") (pinfunction "1_1") (pintype "passive"))
    )
    (net (code "101") (name "Net-(R77-Pad2)") (class "Default")
      (node (ref "R77") (pin "2") (pinfunction "2_2") (pintype "passive"))
      (node (ref "R78") (pin "1") (pinfunction "1_1") (pintype "passive"))
    )
    (net (code "102") (name "Net-(R78-Pad2)") (class "Default")
      (node (ref "R78") (pin "2") (pinfunction "2_2") (pintype "passive"))
      (node (ref "R79") (pin "1") (pinfunction "1_1") (pintype "passive"))
    )
    (net (code "103") (name "Net-(R84-Pad2)") (class "Default")
      (node (ref "R84") (pin "2") (pinfunction "2_2") (pintype "passive"))
      (node (ref "R85") (pin "1") (pinfunction "1_1") (pintype "passive"))
    )
    (net (code "104") (name "Net-(R85-Pad2)") (class "Default")
      (node (ref "R85") (pin "2") (pinfunction "2_2") (pintype "passive"))
      (node (ref "R86") (pin "1") (pinfunction "1_1") (pintype "passive"))
    )
    (net (code "105") (name "Net-(R86-Pad2)") (class "Default")
      (node (ref "R86") (pin "2") (pinfunction "2_2") (pintype "passive"))
      (node (ref "R87") (pin "1") (pinfunction "1_1") (pintype "passive"))
    )
    (net (code "106") (name "Net-(R100-Pad2)") (class "Default")
      (node (ref "R100") (pin "2") (pinfunction "2_2") (pintype "passive"))
      (node (ref "R101") (pin "1") (pinfunction "1_1") (pintype "passive"))
    )
    (net (code "107") (name "Net-(R101-Pad2)") (class "Default")
      (node (ref "R101") (pin "2") (pinfunction "2_2") (pintype "passive"))
      (node (ref "R102") (pin "1") (pinfunction "1_1") (pintype "passive"))
    )
    (net (code "108") (name "Net-(R102-Pad2)") (class "Default")
      (node (ref "R102") (pin "2") (pinfunction "2_2") (pintype "passive"))
      (node (ref "R103") (pin "1") (pinfunction "1_1") (pintype "passive"))
    )
    (net (code "109") (name "Net-(R116-Pad2)") (class "Default")
      (node (ref "R116") (pin "2") (pinfunction "2_2") (pintype "passive"))
      (node (ref "R117") (pin "1") (pinfunction "1_1") (pintype "passive"))
    )
    (net (code "110") (name "Net-(R117-Pad2)") (class "Default")
      (node (ref "R117") (pin "2") (pinfunction "2_2") (pintype "passive"))
      (node (ref "R118") (pin "1") (pinfunction "1_1") (pintype "passive"))
    )
    (net (code "111") (name "Net-(R118-Pad2)") (class "Default")
      (node (ref "R118") (pin "2") (pinfunction "2_2") (pintype "passive"))
      (node (ref "R119") (pin "1") (pinfunction "1_1") (pintype "passive"))
    )
    (net (code "112") (name "OUT_1") (class "Default")
      (node (ref "K1") (pin "4") (pinfunction "4_4") (pintype "passive"))
      (node (ref "K1") (pin "5") (pinfunction "5_5") (pintype "passive"))
      (node (ref "R25") (pin "1") (pinfunction "1_1") (pintype "passive"))
      (node (ref "R34") (pin "1") (pinfunction "1_1") (pintype "passive"))
      (node (ref "R35") (pin "1") (pinfunction "1_1") (pintype "passive"))
      (node (ref "R36") (pin "1") (pinfunction "1_1") (pintype "passive"))
    )
    (net (code "113") (name "OUT_2") (class "Default")
      (node (ref "K2") (pin "4") (pinfunction "4_4") (pintype "passive"))
      (node (ref "K2") (pin "5") (pinfunction "5_5") (pintype "passive"))
      (node (ref "R32") (pin "1") (pinfunction "1_1") (pintype "passive"))
      (node (ref "R50") (pin "1") (pinfunction "1_1") (pintype "passive"))
      (node (ref "R51") (pin "1") (pinfunction "1_1") (pintype "passive"))
      (node (ref "R52") (pin "1") (pinfunction "1_1") (pintype "passive"))
    )
    (net (code "114") (name "OUT_3") (class "Default")
      (node (ref "K3") (pin "4") (pinfunction "4_4") (pintype "passive"))
      (node (ref "K3") (pin "5") (pinfunction "5_5") (pintype "passive"))
      (node (ref "R31") (pin "1") (pinfunction "1_1") (pintype "passive"))
      (node (ref "R66") (pin "1") (pinfunction "1_1") (pintype "passive"))
      (node (ref "R67") (pin "1") (pinfunction "1_1") (pintype "passive"))
      (node (ref "R68") (pin "1") (pinfunction "1_1") (pintype "passive"))
    )
    (net (code "115") (name "OUT_4") (class "Default")
      (node (ref "K4") (pin "4") (pinfunction "4_4") (pintype "passive"))
      (node (ref "K4") (pin "5") (pinfunction "5_5") (pintype "passive"))
      (node (ref "R30") (pin "1") (pinfunction "1_1") (pintype "passive"))
      (node (ref "R82") (pin "1") (pinfunction "1_1") (pintype "passive"))
      (node (ref "R83") (pin "1") (pinfunction "1_1") (pintype "passive"))
      (node (ref "R84") (pin "1") (pinfunction "1_1") (pintype "passive"))
    )
    (net (code "116") (name "OUT_5") (class "Default")
      (node (ref "K5") (pin "4") (pinfunction "4_4") (pintype "passive"))
      (node (ref "K5") (pin "5") (pinfunction "5_5") (pintype "passive"))
      (node (ref "R26") (pin "1") (pinfunction "1_1") (pintype "passive"))
      (node (ref "R42") (pin "1") (pinfunction "1_1") (pintype "passive"))
      (node (ref "R43") (pin "1") (pinfunction "1_1") (pintype "passive"))
      (node (ref "R44") (pin "1") (pinfunction "1_1") (pintype "passive"))
    )
    (net (code "117") (name "OUT_6") (class "Default")
      (node (ref "K6") (pin "4") (pinfunction "4_4") (pintype "passive"))
      (node (ref "K6") (pin "5") (pinfunction "5_5") (pintype "passive"))
      (node (ref "R27") (pin "1") (pinfunction "1_1") (pintype "passive"))
      (node (ref "R74") (pin "1") (pinfunction "1_1") (pintype "passive"))
      (node (ref "R75") (pin "1") (pinfunction "1_1") (pintype "passive"))
      (node (ref "R76") (pin "1") (pinfunction "1_1") (pintype "passive"))
    )
    (net (code "118") (name "OUT_7") (class "Default")
      (node (ref "K7") (pin "4") (pinfunction "4_4") (pintype "passive"))
      (node (ref "K7") (pin "5") (pinfunction "5_5") (pintype "passive"))
      (node (ref "R100") (pin "1") (pinfunction "1_1") (pintype "passive"))
      (node (ref "R28") (pin "1") (pinfunction "1_1") (pintype "passive"))
      (node (ref "R98") (pin "1") (pinfunction "1_1") (pintype "passive"))
      (node (ref "R99") (pin "1") (pinfunction "1_1") (pintype "passive"))
    )
    (net (code "119") (name "OUT_8") (class "Default")
      (node (ref "K8") (pin "4") (pinfunction "4_4") (pintype "passive"))
      (node (ref "K8") (pin "5") (pinfunction "5_5") (pintype "passive"))
      (node (ref "R114") (pin "1") (pinfunction "1_1") (pintype "passive"))
      (node (ref "R115") (pin "1") (pinfunction "1_1") (pintype "passive"))
      (node (ref "R116") (pin "1") (pinfunction "1_1") (pintype "passive"))
      (node (ref "R29") (pin "1") (pinfunction "1_1") (pintype "passive"))
    )
    (net (code "120") (name "RELAY_1") (class "Default")
      (node (ref "D1") (pin "A") (pinfunction "A_A") (pintype "passive"))
      (node (ref "K1") (pin "1") (pinfunction "1_1") (pintype "passive"))
      (node (ref "R24") (pin "2") (pinfunction "2_2") (pintype "passive"))
    )
    (net (code "121") (name "RELAY_2") (class "Default")
      (node (ref "D2") (pin "A") (pinfunction "A_A") (pintype "passive"))
      (node (ref "K2") (pin "1") (pinfunction "1_1") (pintype "passive"))
      (node (ref "R23") (pin "2") (pinfunction "2_2") (pintype "passive"))
    )
    (net (code "122") (name "RELAY_3") (class "Default")
      (node (ref "D3") (pin "A") (pinfunction "A_A") (pintype "passive"))
      (node (ref "K3") (pin "1") (pinfunction "1_1") (pintype "passive"))
      (node (ref "R22") (pin "2") (pinfunction "2_2") (pintype "passive"))
    )
    (net (code "123") (name "RELAY_4") (class "Default")
      (node (ref "D4") (pin "A") (pinfunction "A_A") (pintype "passive"))
      (node (ref "K4") (pin "1") (pinfunction "1_1") (pintype "passive"))
      (node (ref "R21") (pin "2") (pinfunction "2_2") (pintype "passive"))
    )
    (net (code "124") (name "RELAY_5") (class "Default")
      (node (ref "D5") (pin "A") (pinfunction "A_A") (pintype "passive"))
      (node (ref "K5") (pin "1") (pinfunction "1_1") (pintype "passive"))
      (node (ref "R20") (pin "2") (pinfunction "2_2") (pintype "passive"))
    )
    (net (code "125") (name "RELAY_6") (class "Default")
      (node (ref "D6") (pin "A") (pinfunction "A_A") (pintype "passive"))
      (node (ref "K6") (pin "1") (pinfunction "1_1") (pintype "passive"))
      (node (ref "R19") (pin "2") (pinfunction "2_2") (pintype "passive"))
    )
    (net (code "126") (name "RELAY_7") (class "Default")
      (node (ref "D7") (pin "A") (pinfunction "A_A") (pintype "passive"))
      (node (ref "K7") (pin "1") (pinfunction "1_1") (pintype "passive"))
      (node (ref "R18") (pin "2") (pinfunction "2_2") (pintype "passive"))
    )
    (net (code "127") (name "RELAY_8") (class "Default")
      (node (ref "D8") (pin "A") (pinfunction "A_A") (pintype "passive"))
      (node (ref "K8") (pin "1") (pinfunction "1_1") (pintype "passive"))
      (node (ref "R17") (pin "2") (pinfunction "2_2") (pintype "passive"))
    )
    (net (code "128") (name "REL_0") (class "Default")
      (node (ref "IC3") (pin "8") (pinfunction "8B_8") (pintype "bidirectional"))
      (node (ref "IC4") (pin "17") (pinfunction "IO1.0_17") (pintype "bidirectional"))
    )
    (net (code "129") (name "REL_1") (class "Default")
      (node (ref "IC3") (pin "7") (pinfunction "7B_7") (pintype "bidirectional"))
      (node (ref "IC4") (pin "18") (pinfunction "IO1.1_18") (pintype "bidirectional"))
    )
    (net (code "130") (name "REL_2") (class "Default")
      (node (ref "IC3") (pin "6") (pinfunction "6B_6") (pintype "bidirectional"))
      (node (ref "IC4") (pin "19") (pinfunction "IO1.2_19") (pintype "bidirectional"))
    )
    (net (code "131") (name "REL_3") (class "Default")
      (node (ref "IC3") (pin "5") (pinfunction "5B_5") (pintype "bidirectional"))
      (node (ref "IC4") (pin "20") (pinfunction "IO1.3_20") (pintype "bidirectional"))
    )
    (net (code "132") (name "REL_4") (class "Default")
      (node (ref "IC3") (pin "4") (pinfunction "4B_4") (pintype "bidirectional"))
      (node (ref "IC4") (pin "21") (pinfunction "IO1.4_21") (pintype "bidirectional"))
    )
    (net (code "133") (name "REL_5") (class "Default")
      (node (ref "IC3") (pin "3") (pinfunction "3B_3") (pintype "bidirectional"))
      (node (ref "IC4") (pin "22") (pinfunction "IO1.5_22") (pintype "bidirectional"))
    )
    (net (code "134") (name "REL_6") (class "Default")
      (node (ref "IC3") (pin "2") (pinfunction "2B_2") (pintype "bidirectional"))
      (node (ref "IC4") (pin "23") (pinfunction "IO1.6_23") (pintype "bidirectional"))
    )
    (net (code "135") (name "REL_7") (class "Default")
      (node (ref "IC3") (pin "1") (pinfunction "1B_1") (pintype "bidirectional"))
      (node (ref "IC4") (pin "24") (pinfunction "IO1.7_24") (pintype "bidirectional"))
    )
    (net (code "136") (name "RX_CH1") (class "Default")
      (node (ref "IC6") (pin "8") (pinfunction "RX_8") (pintype "bidirectional"))
    )
    (net (code "137") (name "RX_CH2") (class "Default")
      (node (ref "IC8") (pin "8") (pinfunction "RX_8") (pintype "bidirectional"))
    )
    (net (code "138") (name "RX_CH3") (class "Default")
      (node (ref "IC10") (pin "8") (pinfunction "RX_8") (pintype "bidirectional"))
    )
    (net (code "139") (name "RX_CH4") (class "Default")
      (node (ref "IC12") (pin "8") (pinfunction "RX_8") (pintype "bidirectional"))
    )
    (net (code "140") (name "RX_CH5") (class "Default")
      (node (ref "IC7") (pin "8") (pinfunction "RX_8") (pintype "bidirectional"))
    )
    (net (code "141") (name "RX_CH6") (class "Default")
      (node (ref "IC11") (pin "8") (pinfunction "RX_8") (pintype "bidirectional"))
    )
    (net (code "142") (name "RX_CH7") (class "Default")
      (node (ref "IC14") (pin "8") (pinfunction "RX_8") (pintype "bidirectional"))
    )
    (net (code "143") (name "RX_CH8") (class "Default")
      (node (ref "IC16") (pin "8") (pinfunction "RX_8") (pintype "bidirectional"))
    )
    (net (code "144") (name "TX_CH1") (class "Default")
      (node (ref "IC6") (pin "6") (pinfunction "TX_6") (pintype "bidirectional"))
      (node (ref "OPT1") (pin "2") (pinfunction "2_2") (pintype "passive"))
    )
    (net (code "145") (name "TX_CH2") (class "Default")
      (node (ref "IC8") (pin "6") (pinfunction "TX_6") (pintype "bidirectional"))
      (node (ref "OPT1") (pin "4") (pinfunction "4_4") (pintype "passive"))
    )
    (net (code "146") (name "TX_CH3") (class "Default")
      (node (ref "IC10") (pin "6") (pinfunction "TX_6") (pintype "bidirectional"))
      (node (ref "OPT1") (pin "6") (pinfunction "6_6") (pintype "passive"))
    )
    (net (code "147") (name "TX_CH4") (class "Default")
      (node (ref "IC12") (pin "6") (pinfunction "TX_6") (pintype "bidirectional"))
      (node (ref "OPT1") (pin "8") (pinfunction "8_8") (pintype "passive"))
    )
    (net (code "148") (name "TX_CH5") (class "Default")
      (node (ref "IC7") (pin "6") (pinfunction "TX_6") (pintype "bidirectional"))
      (node (ref "OPT2") (pin "2") (pinfunction "2_2") (pintype "passive"))
    )
    (net (code "149") (name "TX_CH6") (class "Default")
      (node (ref "IC11") (pin "6") (pinfunction "TX_6") (pintype "bidirectional"))
      (node (ref "OPT2") (pin "4") (pinfunction "4_4") (pintype "passive"))
    )
    (net (code "150") (name "TX_CH7") (class "Default")
      (node (ref "IC14") (pin "6") (pinfunction "TX_6") (pintype "bidirectional"))
      (node (ref "OPT2") (pin "6") (pinfunction "6_6") (pintype "passive"))
    )
    (net (code "151") (name "TX_CH8") (class "Default")
      (node (ref "IC16") (pin "6") (pinfunction "TX_6") (pintype "bidirectional"))
      (node (ref "OPT2") (pin "8") (pinfunction "8_8") (pintype "passive"))
    )
    (net (code "152") (name "TX_MUX1") (class "Default")
      (node (ref "IC9") (pin "4") (pinfunction "D0_4") (pintype "bidirectional"))
      (node (ref "OPT1") (pin "16") (pinfunction "16_16") (pintype "passive"))
      (node (ref "R89") (pin "1") (pinfunction "1_1") (pintype "passive"))
    )
    (net (code "153") (name "TX_MUX2") (class "Default")
      (node (ref "IC9") (pin "3") (pinfunction "D1_3") (pintype "bidirectional"))
      (node (ref "OPT1") (pin "14") (pinfunction "14_14") (pintype "passive"))
      (node (ref "R89") (pin "2") (pinfunction "2_2") (pintype "passive"))
    )
    (net (code "154") (name "TX_MUX3") (class "Default")
      (node (ref "IC9") (pin "2") (pinfunction "D2_2") (pintype "bidirectional"))
      (node (ref "OPT1") (pin "12") (pinfunction "12_12") (pintype "passive"))
      (node (ref "R89") (pin "3") (pinfunction "3_3") (pintype "passive"))
    )
    (net (code "155") (name "TX_MUX4") (class "Default")
      (node (ref "IC9") (pin "1") (pinfunction "D3_1") (pintype "bidirectional"))
      (node (ref "OPT1") (pin "10") (pinfunction "10_10") (pintype "passive"))
      (node (ref "R89") (pin "4") (pinfunction "4_4") (pintype "passive"))
    )
    (net (code "156") (name "TX_MUX5") (class "Default")
      (node (ref "IC9") (pin "15") (pinfunction "D4_15") (pintype "bidirectional"))
      (node (ref "OPT2") (pin "16") (pinfunction "16_16") (pintype "passive"))
      (node (ref "R90") (pin "1") (pinfunction "1_1") (pintype "passive"))
    )
    (net (code "157") (name "TX_MUX6") (class "Default")
      (node (ref "IC9") (pin "14") (pinfunction "D5_14") (pintype "bidirectional"))
      (node (ref "OPT2") (pin "14") (pinfunction "14_14") (pintype "passive"))
      (node (ref "R90") (pin "2") (pinfunction "2_2") (pintype "passive"))
    )
    (net (code "158") (name "TX_MUX7") (class "Default")
      (node (ref "IC9") (pin "13") (pinfunction "D6_13") (pintype "bidirectional"))
      (node (ref "OPT2") (pin "12") (pinfunction "12_12") (pintype "passive"))
      (node (ref "R90") (pin "3") (pinfunction "3_3") (pintype "passive"))
    )
    (net (code "159") (name "TX_MUX8") (class "Default")
      (node (ref "IC9") (pin "12") (pinfunction "D7_12") (pintype "bidirectional"))
      (node (ref "OPT2") (pin "10") (pinfunction "10_10") (pintype "passive"))
      (node (ref "R90") (pin "4") (pinfunction "4_4") (pintype "passive"))
    )
    (net (code "160") (name "UART0_RX") (class "Default")
      (node (ref "J1") (pin "10") (pinfunction "10_10") (pintype "bidirectional"))
    )
    (net (code "161") (name "UART0_TX") (class "Default")
      (node (ref "J1") (pin "11") (pinfunction "11_11") (pintype "bidirectional"))
      (node (ref "R91") (pin "2") (pinfunction "2_2") (pintype "passive"))
      (node (ref "R92") (pin "2") (pinfunction "2_2") (pintype "passive"))
    )
    (net (code "162") (name "unconnected-(IC4-INTA-Pad16)") (class "Default")
      (node (ref "IC4") (pin "16") (pinfunction "INTA_16") (pintype "bidirectional"))
    )
    (net (code "163") (name "unconnected-(IC4-INTB-Pad15)") (class "Default")
      (node (ref "IC4") (pin "15") (pinfunction "INTB_15") (pintype "bidirectional"))
    )
    (net (code "164") (name "unconnected-(IC4-IO2.4-Pad1)") (class "Default")
      (node (ref "IC4") (pin "1") (pinfunction "IO2.4_1") (pintype "bidirectional"))
    )
    (net (code "165") (name "unconnected-(IC4-IO2.5-Pad2)") (class "Default")
      (node (ref "IC4") (pin "2") (pinfunction "IO2.5_2") (pintype "bidirectional"))
    )
    (net (code "166") (name "unconnected-(IC4-IO2.6-Pad3)") (class "Default")
      (node (ref "IC4") (pin "3") (pinfunction "IO2.6_3") (pintype "bidirectional"))
    )
    (net (code "167") (name "unconnected-(IC4-IO2.7-Pad4)") (class "Default")
      (node (ref "IC4") (pin "4") (pinfunction "IO2.7_4") (pintype "bidirectional"))
    )
    (net (code "168") (name "unconnected-(IC6-PF-Pad7)") (class "Default")
      (node (ref "IC6") (pin "7") (pinfunction "PF_7") (pintype "bidirectional"))
    )
    (net (code "169") (name "unconnected-(IC7-PF-Pad7)") (class "Default")
      (node (ref "IC7") (pin "7") (pinfunction "PF_7") (pintype "bidirectional"))
    )
    (net (code "170") (name "unconnected-(IC8-PF-Pad7)") (class "Default")
      (node (ref "IC8") (pin "7") (pinfunction "PF_7") (pintype "bidirectional"))
    )
    (net (code "171") (name "unconnected-(IC10-PF-Pad7)") (class "Default")
      (node (ref "IC10") (pin "7") (pinfunction "PF_7") (pintype "bidirectional"))
    )
    (net (code "172") (name "unconnected-(IC11-PF-Pad7)") (class "Default")
      (node (ref "IC11") (pin "7") (pinfunction "PF_7") (pintype "bidirectional"))
    )
    (net (code "173") (name "unconnected-(IC12-PF-Pad7)") (class "Default")
      (node (ref "IC12") (pin "7") (pinfunction "PF_7") (pintype "bidirectional"))
    )
    (net (code "174") (name "unconnected-(IC14-PF-Pad7)") (class "Default")
      (node (ref "IC14") (pin "7") (pinfunction "PF_7") (pintype "bidirectional"))
    )
    (net (code "175") (name "unconnected-(IC16-PF-Pad7)") (class "Default")
      (node (ref "IC16") (pin "7") (pinfunction "PF_7") (pintype "bidirectional"))
    )
    (net (code "176") (name "unconnected-(J1-Pad17)") (class "Default")
      (node (ref "J1") (pin "17") (pinfunction "17_17") (pintype "bidirectional"))
    )
    (net (code "177") (name "unconnected-(J1-Pad18)") (class "Default")
      (node (ref "J1") (pin "18") (pinfunction "18_18") (pintype "bidirectional"))
    )
    (net (code "178") (name "unconnected-(J1-Pad19)") (class "Default")
      (node (ref "J1") (pin "19") (pinfunction "19_19") (pintype "bidirectional"))
    )
    (net (code "179") (name "unconnected-(J1-Pad20)") (class "Default")
      (node (ref "J1") (pin "20") (pinfunction "20_20") (pintype "bidirectional"))
    )
  )
)
